# KST-51.net
KiCad netlist of a schematic drawn in Altium Designer
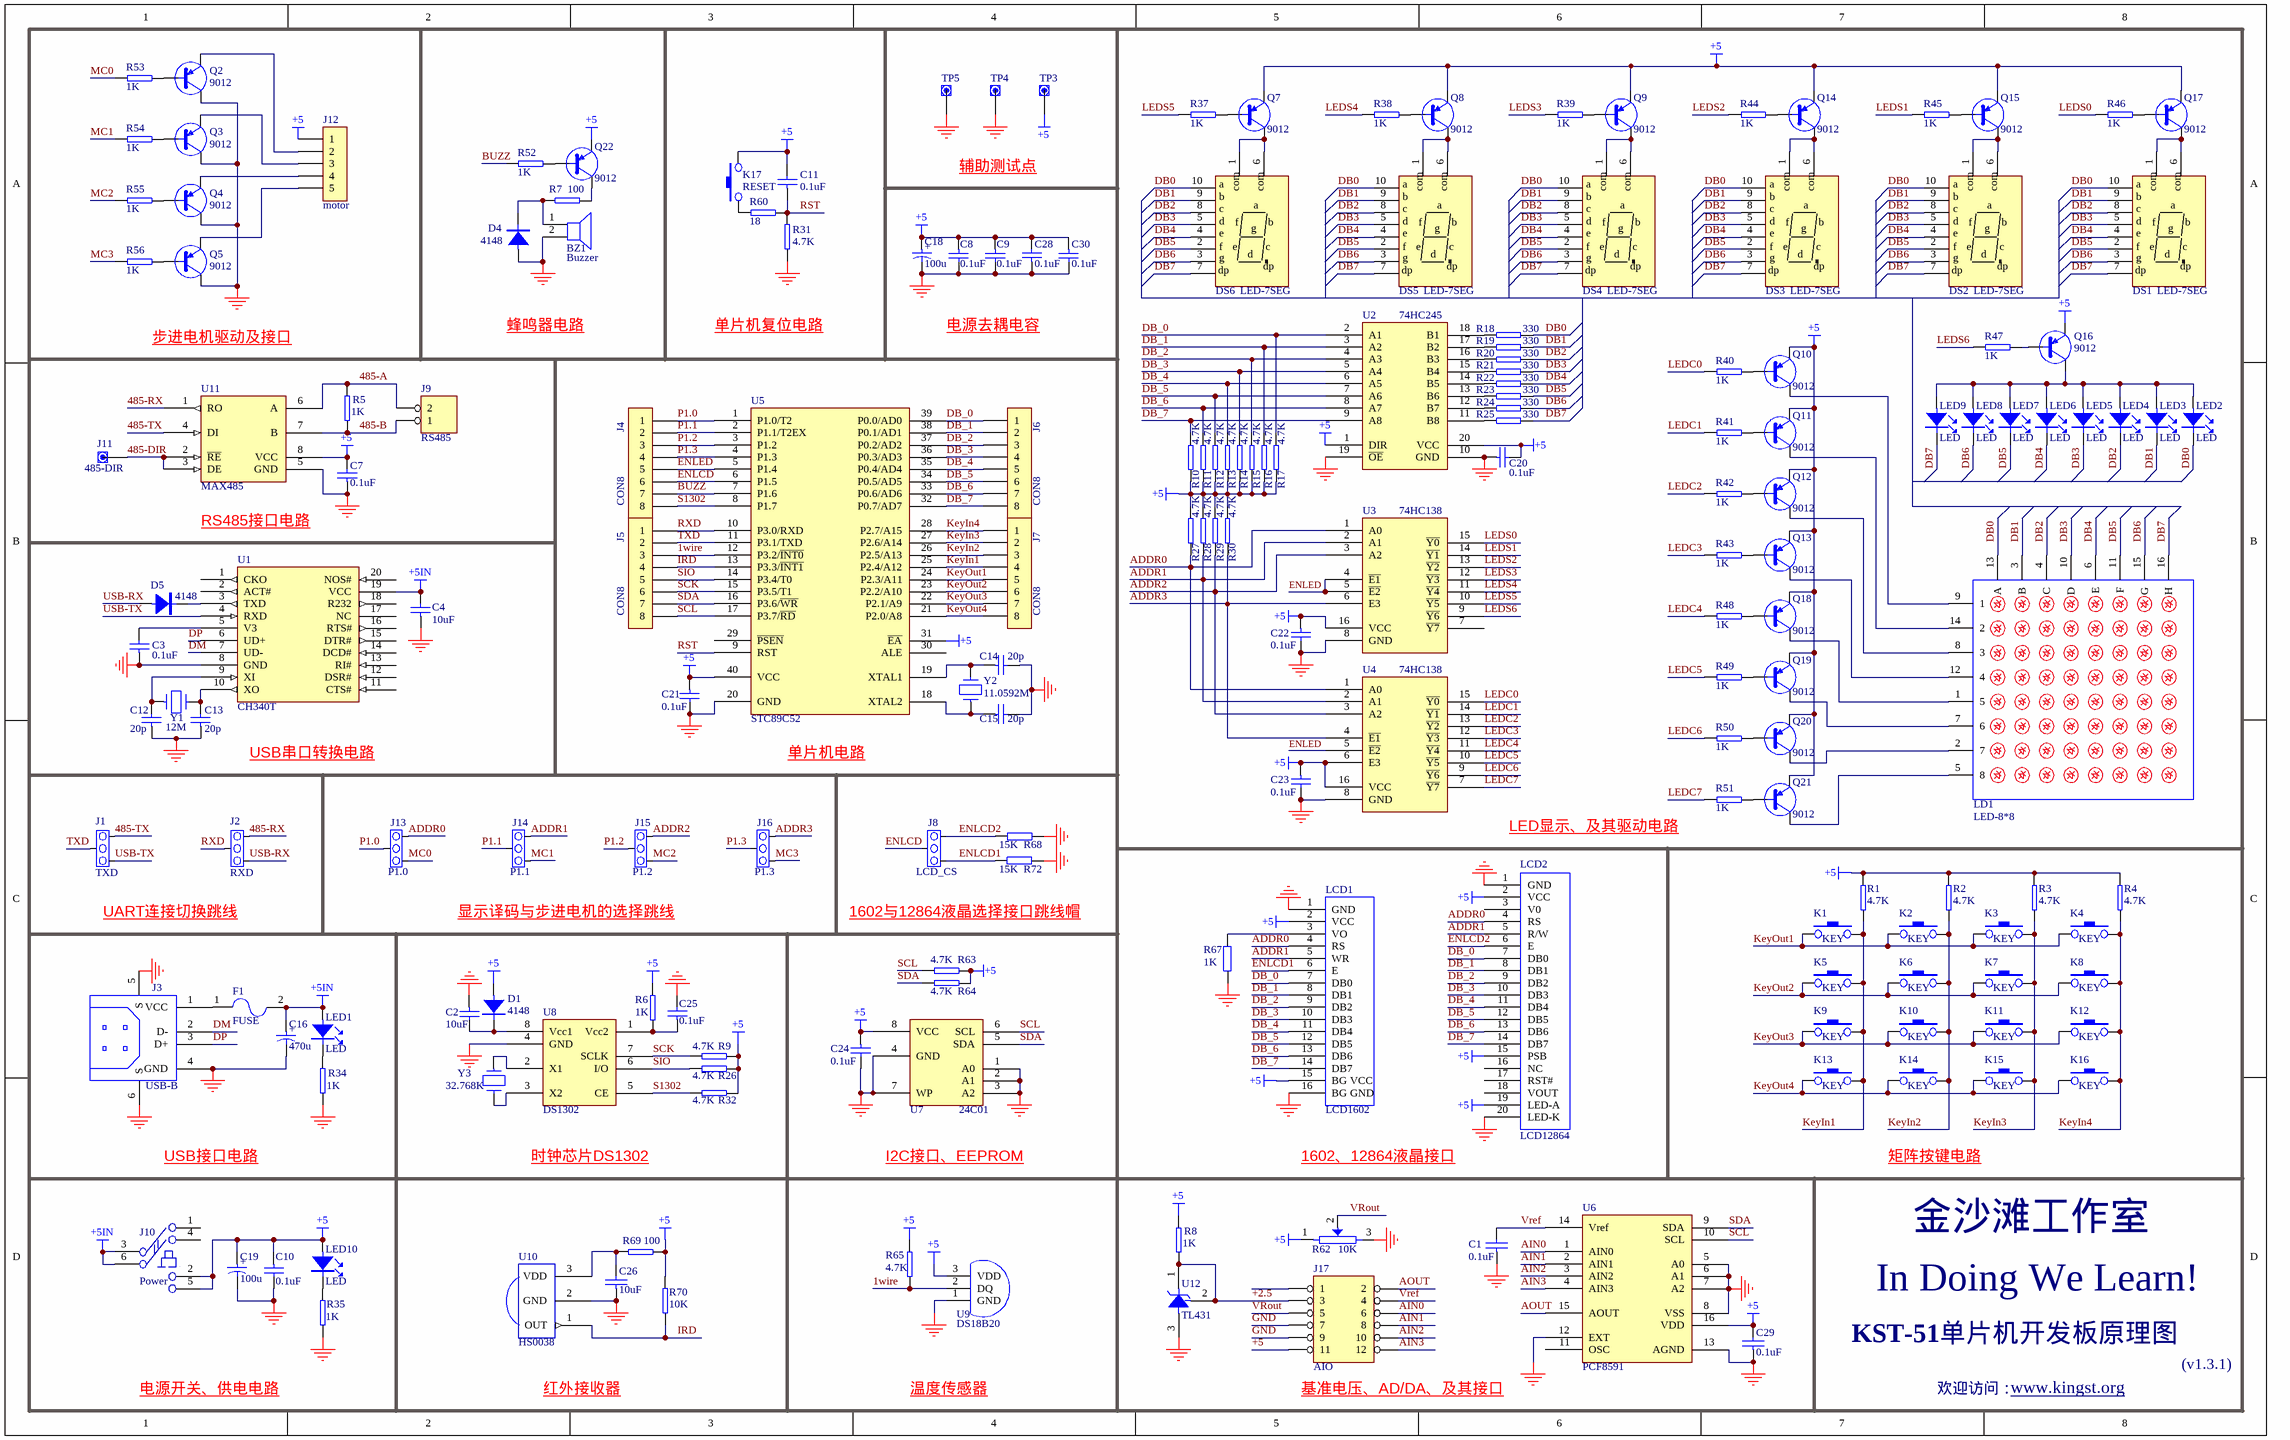
[diagram p0: KST-51开发板原理图.SchDoc]

(export (version "E")
  (design (tool "Eeschema 10.0.6"))
  (components
    (comp (ref "BZ1") (value "Buzzer") (footprint "BUZZ-2") (libsource (lib "*") (part "SPEAKER")))
    (comp (ref "C1")
      (value "0.1uF")
      (footprint "0805C")
      (description "Capacitor")
      (libsource (lib "") (part "CAP_1"))
    )
    (comp (ref "C2") (value "10uF") (footprint "0805C") (libsource (lib "*") (part "CAP")))
    (comp (ref "C3") (value "0.1uF") (footprint "0805C") (libsource (lib "*") (part "CAP")))
    (comp (ref "C4") (value "10uF") (footprint "0805C") (libsource (lib "*") (part "CAP")))
    (comp (ref "C7") (value "0.1uF") (footprint "0805C") (libsource (lib "*") (part "CAP")))
    (comp (ref "C8") (value "0.1uF") (footprint "0805C") (libsource (lib "*") (part "CAP")))
    (comp (ref "C9") (value "0.1uF") (footprint "0805C") (libsource (lib "*") (part "CAP")))
    (comp (ref "C10") (value "0.1uF") (footprint "0805C") (libsource (lib "*") (part "CAP")))
    (comp (ref "C11") (value "0.1uF") (footprint "0805C") (libsource (lib "*") (part "CAP")))
    (comp (ref "C12") (value "20p") (footprint "0805C") (libsource (lib "*") (part "CAP")))
    (comp (ref "C13") (value "20p") (footprint "0805C") (libsource (lib "*") (part "CAP")))
    (comp (ref "C14") (value "20p") (footprint "0805C") (libsource (lib "*") (part "CAP")))
    (comp (ref "C15") (value "20p") (footprint "0805C") (libsource (lib "*") (part "CAP")))
    (comp (ref "C16") (value "470u") (footprint "RB.1/.24") (libsource (lib "*") (part "CAP-P")))
    (comp (ref "C18") (value "100u") (footprint "RB.09/.2") (libsource (lib "*") (part "CAP-P")))
    (comp (ref "C19") (value "100u") (footprint "RB.09/.2") (libsource (lib "*") (part "CAP-P")))
    (comp (ref "C20") (value "0.1uF") (footprint "0805C") (libsource (lib "*") (part "CAP")))
    (comp (ref "C21") (value "0.1uF") (footprint "0805C") (libsource (lib "*") (part "CAP")))
    (comp (ref "C22") (value "0.1uF") (footprint "0805C") (libsource (lib "*") (part "CAP")))
    (comp (ref "C23") (value "0.1uF") (footprint "0805C") (libsource (lib "*") (part "CAP")))
    (comp (ref "C24") (value "0.1uF") (footprint "0805C") (libsource (lib "*") (part "CAP")))
    (comp (ref "C25") (value "0.1uF") (footprint "0805C") (libsource (lib "*") (part "CAP")))
    (comp (ref "C26")
      (value "10uF")
      (footprint "0805C")
      (description "Capacitor")
      (libsource (lib "") (part "CAP_1"))
    )
    (comp (ref "C28") (value "0.1uF") (footprint "0805C") (libsource (lib "*") (part "CAP")))
    (comp (ref "C29")
      (value "0.1uF")
      (footprint "0805C")
      (description "Capacitor")
      (libsource (lib "") (part "CAP_1"))
    )
    (comp (ref "C30") (value "0.1uF") (footprint "0805C") (libsource (lib "*") (part "CAP")))
    (comp (ref "D1") (value "4148") (footprint "1206D") (libsource (lib "*") (part "DIODE")))
    (comp (ref "D4") (value "4148") (footprint "1206D") (libsource (lib "*") (part "DIODE")))
    (comp (ref "D5") (value "4148") (footprint "1206D") (libsource (lib "*") (part "DIODE")))
    (comp (ref "DS1")
      (value "LED-7SEG")
      (footprint "LED-C7")
      (description "Seven-Segment Display, Right Hand Decimal")
      (libsource (lib "*") (part "LED-7SEG"))
    )
    (comp (ref "DS2")
      (value "LED-7SEG")
      (footprint "LED-C7")
      (description "Seven-Segment Display, Right Hand Decimal")
      (libsource (lib "*") (part "LED-7SEG"))
    )
    (comp (ref "DS3")
      (value "LED-7SEG")
      (footprint "LED-C7")
      (description "Seven-Segment Display, Right Hand Decimal")
      (libsource (lib "*") (part "LED-7SEG"))
    )
    (comp (ref "DS4")
      (value "LED-7SEG")
      (footprint "LED-C7")
      (description "Seven-Segment Display, Right Hand Decimal")
      (libsource (lib "*") (part "LED-7SEG"))
    )
    (comp (ref "DS5")
      (value "LED-7SEG")
      (footprint "LED-C7")
      (description "Seven-Segment Display, Right Hand Decimal")
      (libsource (lib "*") (part "LED-7SEG"))
    )
    (comp (ref "DS6")
      (value "LED-7SEG")
      (footprint "LED-C7")
      (description "Seven-Segment Display, Right Hand Decimal")
      (libsource (lib "*") (part "LED-7SEG"))
    )
    (comp (ref "F1") (value "FUSE") (footprint "1812") (libsource (lib "*") (part "FUSE")))
    (comp (ref "J1") (value "TXD") (footprint "JP3*1") (libsource (lib "*") (part "JP-3")))
    (comp (ref "J2") (value "RXD") (footprint "JP3*1") (libsource (lib "*") (part "JP-3")))
    (comp (ref "J3")
      (value "USB-B")
      (footprint "USB-B")
      (description "USB B型插座")
      (libsource (lib "*") (part "USB-B"))
    )
    (comp (ref "J4")
      (value "CON8")
      (footprint "SIP8")
      (description "Connector")
      (libsource (lib "") (part "CON8_1"))
    )
    (comp (ref "J5")
      (value "CON8")
      (footprint "SIP8")
      (description "Connector")
      (libsource (lib "") (part "CON8_1"))
    )
    (comp (ref "J6")
      (value "CON8")
      (footprint "SIP8")
      (description "Connector")
      (libsource (lib "*") (part "CON8"))
    )
    (comp (ref "J7")
      (value "CON8")
      (footprint "SIP8")
      (description "Connector")
      (libsource (lib "*") (part "CON8"))
    )
    (comp (ref "J8") (value "LCD_CS") (footprint "JP3*1") (libsource (lib "*") (part "JP-3")))
    (comp (ref "J9")
      (value "RS485")
      (footprint "PLUG2-5.08")
      (description "Connector 2p")
      (libsource (lib "schOthers") (part "CON2"))
    )
    (comp (ref "J10")
      (value "Power")
      (description "Self-locking button")
      (libsource (lib "schOthers") (part "KEY-SL"))
    )
    (comp (ref "J11")
      (value "485-DIR")
      (footprint "TP")
      (description "Test Point")
      (libsource (lib "schOthers") (part "TP"))
    )
    (comp (ref "J12")
      (value "motor")
      (footprint "PLUG-S5")
      (description "Connector")
      (libsource (lib "*") (part "CON5"))
    )
    (comp (ref "J13") (value "P1.0") (footprint "JP3*1") (libsource (lib "*") (part "JP-3")))
    (comp (ref "J14") (value "P1.1") (footprint "JP3*1") (libsource (lib "*") (part "JP-3")))
    (comp (ref "J15") (value "P1.2") (footprint "JP3*1") (libsource (lib "*") (part "JP-3")))
    (comp (ref "J16") (value "P1.3") (footprint "JP3*1") (libsource (lib "*") (part "JP-3")))
    (comp (ref "J17")
      (value "AIO")
      (footprint "IDC6X2-M")
      (description "Connector 6*2p")
      (libsource (lib "schOthers") (part "CON6X2"))
    )
    (comp (ref "K1") (value "KEY") (footprint "KEY-6*6") (libsource (lib "*") (part "KEY")))
    (comp (ref "K2") (value "KEY") (footprint "KEY-6*6") (libsource (lib "*") (part "KEY")))
    (comp (ref "K3") (value "KEY") (footprint "KEY-6*6") (libsource (lib "*") (part "KEY")))
    (comp (ref "K4") (value "KEY") (footprint "KEY-6*6") (libsource (lib "*") (part "KEY")))
    (comp (ref "K5") (value "KEY") (footprint "KEY-6*6") (libsource (lib "*") (part "KEY")))
    (comp (ref "K6") (value "KEY") (footprint "KEY-6*6") (libsource (lib "*") (part "KEY")))
    (comp (ref "K7") (value "KEY") (footprint "KEY-6*6") (libsource (lib "*") (part "KEY")))
    (comp (ref "K8") (value "KEY") (footprint "KEY-6*6") (libsource (lib "*") (part "KEY")))
    (comp (ref "K9") (value "KEY") (footprint "KEY-6*6") (libsource (lib "*") (part "KEY")))
    (comp (ref "K10") (value "KEY") (footprint "KEY-6*6") (libsource (lib "*") (part "KEY")))
    (comp (ref "K11") (value "KEY") (footprint "KEY-6*6") (libsource (lib "*") (part "KEY")))
    (comp (ref "K12") (value "KEY") (footprint "KEY-6*6") (libsource (lib "*") (part "KEY")))
    (comp (ref "K13") (value "KEY") (footprint "KEY-6*6") (libsource (lib "*") (part "KEY")))
    (comp (ref "K14") (value "KEY") (footprint "KEY-6*6") (libsource (lib "*") (part "KEY")))
    (comp (ref "K15") (value "KEY") (footprint "KEY-6*6") (libsource (lib "*") (part "KEY")))
    (comp (ref "K16") (value "KEY") (footprint "KEY-6*6") (libsource (lib "*") (part "KEY")))
    (comp (ref "K17") (value "RESET") (footprint "KEY-6*6") (libsource (lib "*") (part "KEY")))
    (comp (ref "LCD1") (value "LCD1602") (footprint "LCD1602") (libsource (lib "*") (part "LCD1602")))
    (comp (ref "LCD2")
      (value "LCD12864")
      (footprint "SIP20")
      (description "20pin 128*64 LCD")
      (libsource (lib "schOthers") (part "LCD-12864"))
    )
    (comp (ref "LD1") (value "LED-8*8") (footprint "LED-8*8") (libsource (lib "*") (part "LED-8*8")))
    (comp (ref "LED1") (value "LED") (footprint "0805LED") (libsource (lib "*") (part "LED")))
    (comp (ref "LED2") (value "LED") (footprint "0805LED") (libsource (lib "*") (part "LED")))
    (comp (ref "LED3") (value "LED") (footprint "0805LED") (libsource (lib "*") (part "LED")))
    (comp (ref "LED4") (value "LED") (footprint "0805LED") (libsource (lib "*") (part "LED")))
    (comp (ref "LED5") (value "LED") (footprint "0805LED") (libsource (lib "*") (part "LED")))
    (comp (ref "LED6") (value "LED") (footprint "0805LED") (libsource (lib "*") (part "LED")))
    (comp (ref "LED7") (value "LED") (footprint "0805LED") (libsource (lib "*") (part "LED")))
    (comp (ref "LED8") (value "LED") (footprint "0805LED") (libsource (lib "*") (part "LED")))
    (comp (ref "LED9") (value "LED") (footprint "0805LED") (libsource (lib "*") (part "LED")))
    (comp (ref "LED10") (value "LED") (footprint "0805LED") (libsource (lib "*") (part "LED")))
    (comp (ref "Q2") (value "9012") (footprint "SOT-23-2N") (libsource (lib "*") (part "2N-PNP")))
    (comp (ref "Q3") (value "9012") (footprint "SOT-23-2N") (libsource (lib "*") (part "2N-PNP")))
    (comp (ref "Q4") (value "9012") (footprint "SOT-23-2N") (libsource (lib "*") (part "2N-PNP")))
    (comp (ref "Q5") (value "9012") (footprint "SOT-23-2N") (libsource (lib "*") (part "2N-PNP")))
    (comp (ref "Q7") (value "9012") (footprint "SOT-23-2N") (libsource (lib "*") (part "2N-PNP")))
    (comp (ref "Q8") (value "9012") (footprint "SOT-23-2N") (libsource (lib "*") (part "2N-PNP")))
    (comp (ref "Q9") (value "9012") (footprint "SOT-23-2N") (libsource (lib "*") (part "2N-PNP")))
    (comp (ref "Q10") (value "9012") (footprint "SOT-23-2N") (libsource (lib "*") (part "2N-PNP")))
    (comp (ref "Q11") (value "9012") (footprint "SOT-23-2N") (libsource (lib "*") (part "2N-PNP")))
    (comp (ref "Q12") (value "9012") (footprint "SOT-23-2N") (libsource (lib "*") (part "2N-PNP")))
    (comp (ref "Q13") (value "9012") (footprint "SOT-23-2N") (libsource (lib "*") (part "2N-PNP")))
    (comp (ref "Q14") (value "9012") (footprint "SOT-23-2N") (libsource (lib "*") (part "2N-PNP")))
    (comp (ref "Q15") (value "9012") (footprint "SOT-23-2N") (libsource (lib "*") (part "2N-PNP")))
    (comp (ref "Q16") (value "9012") (footprint "SOT-23-2N") (libsource (lib "*") (part "2N-PNP")))
    (comp (ref "Q17") (value "9012") (footprint "SOT-23-2N") (libsource (lib "*") (part "2N-PNP")))
    (comp (ref "Q18") (value "9012") (footprint "SOT-23-2N") (libsource (lib "*") (part "2N-PNP")))
    (comp (ref "Q19") (value "9012") (footprint "SOT-23-2N") (libsource (lib "*") (part "2N-PNP")))
    (comp (ref "Q20") (value "9012") (footprint "SOT-23-2N") (libsource (lib "*") (part "2N-PNP")))
    (comp (ref "Q21") (value "9012") (footprint "SOT-23-2N") (libsource (lib "*") (part "2N-PNP")))
    (comp (ref "Q22") (value "9012") (footprint "SOT-23-2N") (libsource (lib "*") (part "2N-PNP")))
    (comp (ref "R1") (value "4.7K") (footprint "0805") (libsource (lib "*") (part "RES2")))
    (comp (ref "R2") (value "4.7K") (footprint "0805") (libsource (lib "*") (part "RES2")))
    (comp (ref "R3") (value "4.7K") (footprint "0805") (libsource (lib "*") (part "RES2")))
    (comp (ref "R4") (value "4.7K") (footprint "0805") (libsource (lib "*") (part "RES2")))
    (comp (ref "R5") (value "1K") (footprint "0805") (libsource (lib "*") (part "RES2")))
    (comp (ref "R6") (value "1K") (footprint "0805") (libsource (lib "*") (part "RES2")))
    (comp (ref "R7") (value "100") (footprint "0805") (libsource (lib "*") (part "RES2")))
    (comp (ref "R8") (value "1K") (footprint "0805") (libsource (lib "*") (part "RES2")))
    (comp (ref "R9") (value "4.7K") (footprint "0805") (libsource (lib "*") (part "RES2")))
    (comp (ref "R10") (value "4.7K") (footprint "0805") (libsource (lib "*") (part "RES2")))
    (comp (ref "R11") (value "4.7K") (footprint "0805") (libsource (lib "*") (part "RES2")))
    (comp (ref "R12") (value "4.7K") (footprint "0805") (libsource (lib "*") (part "RES2")))
    (comp (ref "R13") (value "4.7K") (footprint "0805") (libsource (lib "*") (part "RES2")))
    (comp (ref "R14") (value "4.7K") (footprint "0805") (libsource (lib "*") (part "RES2")))
    (comp (ref "R15") (value "4.7K") (footprint "0805") (libsource (lib "*") (part "RES2")))
    (comp (ref "R16") (value "4.7K") (footprint "0805") (libsource (lib "*") (part "RES2")))
    (comp (ref "R17") (value "4.7K") (footprint "0805") (libsource (lib "*") (part "RES2")))
    (comp (ref "R18") (value "330") (footprint "0805") (libsource (lib "*") (part "RES2")))
    (comp (ref "R19") (value "330") (footprint "0805") (libsource (lib "*") (part "RES2")))
    (comp (ref "R20") (value "330") (footprint "0805") (libsource (lib "*") (part "RES2")))
    (comp (ref "R21") (value "330") (footprint "0805") (libsource (lib "*") (part "RES2")))
    (comp (ref "R22") (value "330") (footprint "0805") (libsource (lib "*") (part "RES2")))
    (comp (ref "R23") (value "330") (footprint "0805") (libsource (lib "*") (part "RES2")))
    (comp (ref "R24") (value "330") (footprint "0805") (libsource (lib "*") (part "RES2")))
    (comp (ref "R25") (value "330") (footprint "0805") (libsource (lib "*") (part "RES2")))
    (comp (ref "R26") (value "4.7K") (footprint "0805") (libsource (lib "*") (part "RES2")))
    (comp (ref "R27") (value "4.7K") (footprint "0805") (libsource (lib "*") (part "RES2")))
    (comp (ref "R28") (value "4.7K") (footprint "0805") (libsource (lib "*") (part "RES2")))
    (comp (ref "R29") (value "4.7K") (footprint "0805") (libsource (lib "*") (part "RES2")))
    (comp (ref "R30") (value "4.7K") (footprint "0805") (libsource (lib "*") (part "RES2")))
    (comp (ref "R31") (value "4.7K") (footprint "0805") (libsource (lib "*") (part "RES2")))
    (comp (ref "R32") (value "4.7K") (footprint "0805") (libsource (lib "*") (part "RES2")))
    (comp (ref "R34") (value "1K") (footprint "0805") (libsource (lib "*") (part "RES2")))
    (comp (ref "R35") (value "1K") (footprint "0805") (libsource (lib "*") (part "RES2")))
    (comp (ref "R37") (value "1K") (footprint "0805") (libsource (lib "*") (part "RES2")))
    (comp (ref "R38") (value "1K") (footprint "0805") (libsource (lib "*") (part "RES2")))
    (comp (ref "R39") (value "1K") (footprint "0805") (libsource (lib "*") (part "RES2")))
    (comp (ref "R40") (value "1K") (footprint "0805") (libsource (lib "*") (part "RES2")))
    (comp (ref "R41") (value "1K") (footprint "0805") (libsource (lib "*") (part "RES2")))
    (comp (ref "R42") (value "1K") (footprint "0805") (libsource (lib "*") (part "RES2")))
    (comp (ref "R43") (value "1K") (footprint "0805") (libsource (lib "*") (part "RES2")))
    (comp (ref "R44") (value "1K") (footprint "0805") (libsource (lib "*") (part "RES2")))
    (comp (ref "R45") (value "1K") (footprint "0805") (libsource (lib "*") (part "RES2")))
    (comp (ref "R46") (value "1K") (footprint "0805") (libsource (lib "*") (part "RES2")))
    (comp (ref "R47") (value "1K") (footprint "0805") (libsource (lib "*") (part "RES2")))
    (comp (ref "R48") (value "1K") (footprint "0805") (libsource (lib "*") (part "RES2")))
    (comp (ref "R49") (value "1K") (footprint "0805") (libsource (lib "*") (part "RES2")))
    (comp (ref "R50") (value "1K") (footprint "0805") (libsource (lib "*") (part "RES2")))
    (comp (ref "R51") (value "1K") (footprint "0805") (libsource (lib "*") (part "RES2")))
    (comp (ref "R52") (value "1K") (footprint "0805") (libsource (lib "*") (part "RES2")))
    (comp (ref "R53") (value "1K") (footprint "0805") (libsource (lib "*") (part "RES2")))
    (comp (ref "R54") (value "1K") (footprint "0805") (libsource (lib "*") (part "RES2")))
    (comp (ref "R55") (value "1K") (footprint "0805") (libsource (lib "*") (part "RES2")))
    (comp (ref "R56") (value "1K") (footprint "0805") (libsource (lib "*") (part "RES2")))
    (comp (ref "R60") (value "18") (footprint "0805") (libsource (lib "*") (part "RES2")))
    (comp (ref "R62") (value "10K") (footprint "VR6") (libsource (lib "*") (part "RES-V")))
    (comp (ref "R63") (value "4.7K") (footprint "0805") (libsource (lib "*") (part "RES2")))
    (comp (ref "R64") (value "4.7K") (footprint "0805") (libsource (lib "*") (part "RES2")))
    (comp (ref "R65") (value "4.7K") (footprint "0805") (libsource (lib "*") (part "RES2")))
    (comp (ref "R67") (value "1K") (footprint "0805") (description "电阻") (libsource (lib "") (part "RES2_1")))
    (comp (ref "R68")
      (value "15K")
      (footprint "0805")
      (description "电阻")
      (libsource (lib "") (part "RES2_1"))
    )
    (comp (ref "R69") (value "100") (footprint "0805") (libsource (lib "*") (part "RES2")))
    (comp (ref "R70") (value "10K") (footprint "0805") (libsource (lib "*") (part "RES2")))
    (comp (ref "R72")
      (value "15K")
      (footprint "0805")
      (description "电阻")
      (libsource (lib "") (part "RES2_1"))
    )
    (comp (ref "TP3")
      (value "+5V")
      (footprint "TP-S")
      (description "电路测试点")
      (libsource (lib "*") (part "TP"))
    )
    (comp (ref "TP4")
      (value "GND")
      (footprint "TP-S")
      (description "电路测试点")
      (libsource (lib "*") (part "TP"))
    )
    (comp (ref "TP5")
      (value "GND")
      (footprint "TP-S")
      (description "电路测试点")
      (libsource (lib "*") (part "TP"))
    )
    (comp (ref "U1")
      (value "CH340T")
      (footprint "SSOP20-5.3")
      (description "USB to UART Bridge Controller")
      (libsource (lib "schChips") (part "CH340T"))
    )
    (comp (ref "U2") (value "74HC245") (footprint "SOP20-400") (libsource (lib "*") (part "74XX245")))
    (comp (ref "U3") (value "74HC138") (footprint "SOP16-240") (libsource (lib "*") (part "74XX138")))
    (comp (ref "U4") (value "74HC138") (footprint "SOP16-240") (libsource (lib "*") (part "74XX138")))
    (comp (ref "U5") (value "STC89C52") (footprint "DIP40-PLUG") (libsource (lib "*") (part "STC89C52")))
    (comp (ref "U6") (value "PCF8591") (footprint "SOP16-400") (libsource (lib "*") (part "PCF8591")))
    (comp (ref "U7") (value "24C01") (footprint "SOP8") (libsource (lib "*") (part "24C01")))
    (comp (ref "U8") (value "DS1302") (footprint "SOP8") (libsource (lib "*") (part "DS1302")))
    (comp (ref "U9") (value "DS18B20") (footprint "TO-92") (libsource (lib "*") (part "DS18B20")))
    (comp (ref "U10")
      (value "HS0038")
      (footprint "HS0038")
      (description "Infrared Receiver")
      (libsource (lib "schChips") (part "HS0038"))
    )
    (comp (ref "U11")
      (value "MAX485")
      (footprint "SOP8-3.9")
      (description "RS-485 Transceiver")
      (libsource (lib "schChips") (part "MAX485"))
    )
    (comp (ref "U12")
      (value "TL431")
      (footprint "SOT-23-3L")
      (description "Adjustable precision shunt regulator, 3p SOT")
      (libsource (lib "schChips") (part "TL431-SOT"))
    )
    (comp (ref "Y1") (value "12M") (footprint "XTAL") (libsource (lib "*") (part "CRYSTAL")))
    (comp (ref "Y2") (value "11.0592M") (footprint "XTAL") (libsource (lib "*") (part "CRYSTAL")))
    (comp (ref "Y3") (value "32.768K") (footprint "XTAL2") (libsource (lib "*") (part "CRYSTAL")))
  )
  (nets
    (net (code "1") (name "+5") (class "Default")
      (node (ref "C10") (pin "1") (pinfunction "1_1") (pintype "passive"))
      (node (ref "C11") (pin "2") (pinfunction "2_2") (pintype "passive"))
      (node (ref "C18") (pin "1") (pinfunction "1_1") (pintype "passive"))
      (node (ref "C19") (pin "1") (pinfunction "1_1") (pintype "passive"))
      (node (ref "C20") (pin "2") (pinfunction "2_2") (pintype "passive"))
      (node (ref "C21") (pin "1") (pinfunction "1_1") (pintype "passive"))
      (node (ref "C22") (pin "1") (pinfunction "1_1") (pintype "passive"))
      (node (ref "C23") (pin "1") (pinfunction "1_1") (pintype "passive"))
      (node (ref "C24") (pin "1") (pinfunction "1_1") (pintype "passive"))
      (node (ref "C28") (pin "2") (pinfunction "2_2") (pintype "passive"))
      (node (ref "C29") (pin "2") (pinfunction "2_2") (pintype "passive"))
      (node (ref "C30") (pin "1") (pinfunction "1_1") (pintype "passive"))
      (node (ref "C7") (pin "2") (pinfunction "2_2") (pintype "passive"))
      (node (ref "C8") (pin "1") (pinfunction "1_1") (pintype "passive"))
      (node (ref "C9") (pin "1") (pinfunction "1_1") (pintype "passive"))
      (node (ref "D1") (pin "A") (pinfunction "1_A") (pintype "passive"))
      (node (ref "J10") (pin "2") (pinfunction "2_2") (pintype "passive"))
      (node (ref "J10") (pin "5") (pinfunction "5_5") (pintype "passive"))
      (node (ref "J12") (pin "1") (pinfunction "1_1") (pintype "passive"))
      (node (ref "J17") (pin "11") (pinfunction "11_11") (pintype "passive"))
      (node (ref "K17") (pin "2") (pinfunction "2_2") (pintype "passive"))
      (node (ref "LCD1") (pin "15") (pinfunction "BG_VCC_15") (pintype "passive"))
      (node (ref "LCD1") (pin "2") (pinfunction "VCC_2") (pintype "passive"))
      (node (ref "LCD2") (pin "15") (pinfunction "PSB_15") (pintype "power_in"))
      (node (ref "LCD2") (pin "19") (pinfunction "LED-A_19") (pintype "power_in"))
      (node (ref "LCD2") (pin "2") (pinfunction "VCC_2") (pintype "power_in"))
      (node (ref "LED10") (pin "A") (pinfunction "1_A") (pintype "passive"))
      (node (ref "Q10") (pin "E") (pinfunction "E_E") (pintype "passive"))
      (node (ref "Q11") (pin "E") (pinfunction "E_E") (pintype "passive"))
      (node (ref "Q12") (pin "E") (pinfunction "E_E") (pintype "passive"))
      (node (ref "Q13") (pin "E") (pinfunction "E_E") (pintype "passive"))
      (node (ref "Q14") (pin "E") (pinfunction "E_E") (pintype "passive"))
      (node (ref "Q15") (pin "E") (pinfunction "E_E") (pintype "passive"))
      (node (ref "Q16") (pin "E") (pinfunction "E_E") (pintype "passive"))
      (node (ref "Q17") (pin "E") (pinfunction "E_E") (pintype "passive"))
      (node (ref "Q18") (pin "E") (pinfunction "E_E") (pintype "passive"))
      (node (ref "Q19") (pin "E") (pinfunction "E_E") (pintype "passive"))
      (node (ref "Q20") (pin "E") (pinfunction "E_E") (pintype "passive"))
      (node (ref "Q21") (pin "E") (pinfunction "E_E") (pintype "passive"))
      (node (ref "Q22") (pin "E") (pinfunction "E_E") (pintype "passive"))
      (node (ref "Q7") (pin "E") (pinfunction "E_E") (pintype "passive"))
      (node (ref "Q8") (pin "E") (pinfunction "E_E") (pintype "passive"))
      (node (ref "Q9") (pin "E") (pinfunction "E_E") (pintype "passive"))
      (node (ref "R1") (pin "2") (pinfunction "2_2") (pintype "passive"))
      (node (ref "R10") (pin "1") (pinfunction "1_1") (pintype "passive"))
      (node (ref "R11") (pin "1") (pinfunction "1_1") (pintype "passive"))
      (node (ref "R12") (pin "1") (pinfunction "1_1") (pintype "passive"))
      (node (ref "R13") (pin "1") (pinfunction "1_1") (pintype "passive"))
      (node (ref "R14") (pin "1") (pinfunction "1_1") (pintype "passive"))
      (node (ref "R15") (pin "1") (pinfunction "1_1") (pintype "passive"))
      (node (ref "R16") (pin "1") (pinfunction "1_1") (pintype "passive"))
      (node (ref "R17") (pin "1") (pinfunction "1_1") (pintype "passive"))
      (node (ref "R2") (pin "2") (pinfunction "2_2") (pintype "passive"))
      (node (ref "R26") (pin "2") (pinfunction "2_2") (pintype "passive"))
      (node (ref "R27") (pin "2") (pinfunction "2_2") (pintype "passive"))
      (node (ref "R28") (pin "2") (pinfunction "2_2") (pintype "passive"))
      (node (ref "R29") (pin "2") (pinfunction "2_2") (pintype "passive"))
      (node (ref "R3") (pin "2") (pinfunction "2_2") (pintype "passive"))
      (node (ref "R30") (pin "2") (pinfunction "2_2") (pintype "passive"))
      (node (ref "R32") (pin "2") (pinfunction "2_2") (pintype "passive"))
      (node (ref "R4") (pin "2") (pinfunction "2_2") (pintype "passive"))
      (node (ref "R6") (pin "2") (pinfunction "2_2") (pintype "passive"))
      (node (ref "R62") (pin "1") (pinfunction "1_1") (pintype "passive"))
      (node (ref "R63") (pin "2") (pinfunction "2_2") (pintype "passive"))
      (node (ref "R64") (pin "2") (pinfunction "2_2") (pintype "passive"))
      (node (ref "R65") (pin "2") (pinfunction "2_2") (pintype "passive"))
      (node (ref "R69") (pin "2") (pinfunction "2_2") (pintype "passive"))
      (node (ref "R70") (pin "1") (pinfunction "1_1") (pintype "passive"))
      (node (ref "R8") (pin "2") (pinfunction "2_2") (pintype "passive"))
      (node (ref "R9") (pin "2") (pinfunction "2_2") (pintype "passive"))
      (node (ref "TP3") (pin "1") (pintype "passive"))
      (node (ref "U11") (pin "8") (pinfunction "VCC_8") (pintype "power_in"))
      (node (ref "U2") (pin "1") (pinfunction "DIR_1") (pintype "passive"))
      (node (ref "U2") (pin "20") (pinfunction "VCC_20") (pintype "passive"))
      (node (ref "U3") (pin "16") (pinfunction "VCC_16") (pintype "passive"))
      (node (ref "U4") (pin "16") (pinfunction "VCC_16") (pintype "passive"))
      (node (ref "U4") (pin "6") (pinfunction "E3_6") (pintype "passive"))
      (node (ref "U5") (pin "31") (pinfunction "~{EA}_31") (pintype "passive"))
      (node (ref "U5") (pin "40") (pinfunction "VCC_40") (pintype "passive"))
      (node (ref "U6") (pin "16") (pinfunction "VDD_16") (pintype "passive"))
      (node (ref "U7") (pin "8") (pinfunction "VCC_8") (pintype "passive"))
      (node (ref "U9") (pin "3") (pinfunction "VDD_3") (pintype "passive"))
    )
    (net (code "2") (name "+5IN") (class "Default")
      (node (ref "C16") (pin "1") (pinfunction "1_1") (pintype "passive"))
      (node (ref "C4") (pin "2") (pinfunction "2_2") (pintype "passive"))
      (node (ref "F1") (pin "2") (pinfunction "2_2") (pintype "passive"))
      (node (ref "J10") (pin "3") (pinfunction "3_3") (pintype "passive"))
      (node (ref "J10") (pin "6") (pinfunction "6_6") (pintype "passive"))
      (node (ref "LED1") (pin "A") (pinfunction "1_A") (pintype "passive"))
      (node (ref "U1") (pin "19") (pinfunction "VCC_19") (pintype "power_in"))
    )
    (net (code "3") (name "/+2.5") (class "Default")
      (node (ref "J17") (pin "3") (pinfunction "3_3") (pintype "passive"))
      (node (ref "R8") (pin "1") (pinfunction "1_1") (pintype "passive"))
      (node (ref "U12") (pin "1") (pinfunction "CATHODE_1") (pintype "power_in"))
      (node (ref "U12") (pin "2") (pinfunction "REF_2") (pintype "passive"))
    )
    (net (code "4") (name "/1wire") (class "Default")
      (node (ref "J5") (pin "3") (pinfunction "3_3") (pintype "passive"))
      (node (ref "R65") (pin "1") (pinfunction "1_1") (pintype "passive"))
      (node (ref "U5") (pin "12") (pinfunction "P3.2/~{INT0}_12") (pintype "passive"))
      (node (ref "U9") (pin "2") (pinfunction "DQ_2") (pintype "passive"))
    )
    (net (code "5") (name "/485-A") (class "Default")
      (node (ref "J9") (pin "2") (pinfunction "2_2") (pintype "passive"))
      (node (ref "R5") (pin "1") (pinfunction "1_1") (pintype "passive"))
      (node (ref "U11") (pin "6") (pinfunction "A_6") (pintype "passive"))
    )
    (net (code "6") (name "/485-B") (class "Default")
      (node (ref "J9") (pin "1") (pinfunction "1_1") (pintype "passive"))
      (node (ref "R5") (pin "2") (pinfunction "2_2") (pintype "passive"))
      (node (ref "U11") (pin "7") (pinfunction "B_7") (pintype "passive"))
    )
    (net (code "7") (name "/485-DIR") (class "Default")
      (node (ref "J11") (pin "1") (pintype "passive"))
      (node (ref "U11") (pin "2") (pinfunction "~{RE}_2") (pintype "input"))
      (node (ref "U11") (pin "3") (pinfunction "DE_3") (pintype "input"))
    )
    (net (code "8") (name "/485-RX") (class "Default")
      (node (ref "J2") (pin "3") (pinfunction "3_3") (pintype "passive"))
      (node (ref "U11") (pin "1") (pinfunction "RO_1") (pintype "output"))
    )
    (net (code "9") (name "/485-TX") (class "Default")
      (node (ref "J1") (pin "3") (pinfunction "3_3") (pintype "passive"))
      (node (ref "U11") (pin "4") (pinfunction "DI_4") (pintype "input"))
    )
    (net (code "10") (name "/ADDR0") (class "Default")
      (node (ref "J13") (pin "1") (pinfunction "1_1") (pintype "passive"))
      (node (ref "LCD1") (pin "4") (pinfunction "RS_4") (pintype "passive"))
      (node (ref "LCD2") (pin "4") (pinfunction "RS_4") (pintype "power_in"))
      (node (ref "R27") (pin "1") (pinfunction "1_1") (pintype "passive"))
      (node (ref "U3") (pin "1") (pinfunction "A0_1") (pintype "passive"))
      (node (ref "U4") (pin "1") (pinfunction "A0_1") (pintype "passive"))
    )
    (net (code "11") (name "/ADDR1") (class "Default")
      (node (ref "J14") (pin "1") (pinfunction "1_1") (pintype "passive"))
      (node (ref "LCD1") (pin "5") (pinfunction "WR_5") (pintype "passive"))
      (node (ref "LCD2") (pin "5") (pinfunction "R/W_5") (pintype "power_in"))
      (node (ref "R28") (pin "1") (pinfunction "1_1") (pintype "passive"))
      (node (ref "U3") (pin "2") (pinfunction "A1_2") (pintype "passive"))
      (node (ref "U4") (pin "2") (pinfunction "A1_2") (pintype "passive"))
    )
    (net (code "12") (name "/ADDR2") (class "Default")
      (node (ref "J15") (pin "1") (pinfunction "1_1") (pintype "passive"))
      (node (ref "R29") (pin "1") (pinfunction "1_1") (pintype "passive"))
      (node (ref "U3") (pin "3") (pinfunction "A2_3") (pintype "passive"))
      (node (ref "U4") (pin "3") (pinfunction "A2_3") (pintype "passive"))
    )
    (net (code "13") (name "/ADDR3") (class "Default")
      (node (ref "J16") (pin "1") (pinfunction "1_1") (pintype "passive"))
      (node (ref "R30") (pin "1") (pinfunction "1_1") (pintype "passive"))
      (node (ref "U3") (pin "6") (pinfunction "E3_6") (pintype "passive"))
      (node (ref "U4") (pin "4") (pinfunction "~{E1}_4") (pintype "passive"))
    )
    (net (code "14") (name "/AIN0") (class "Default")
      (node (ref "J17") (pin "6") (pinfunction "6_6") (pintype "passive"))
      (node (ref "U6") (pin "1") (pinfunction "AIN0_1") (pintype "passive"))
    )
    (net (code "15") (name "/AIN1") (class "Default")
      (node (ref "J17") (pin "8") (pinfunction "8_8") (pintype "passive"))
      (node (ref "U6") (pin "2") (pinfunction "AIN1_2") (pintype "passive"))
    )
    (net (code "16") (name "/AIN2") (class "Default")
      (node (ref "J17") (pin "10") (pinfunction "10_10") (pintype "passive"))
      (node (ref "U6") (pin "3") (pinfunction "AIN2_3") (pintype "passive"))
    )
    (net (code "17") (name "/AIN3") (class "Default")
      (node (ref "J17") (pin "12") (pinfunction "12_12") (pintype "passive"))
      (node (ref "U6") (pin "4") (pinfunction "AIN3_4") (pintype "passive"))
    )
    (net (code "18") (name "/AOUT") (class "Default")
      (node (ref "J17") (pin "2") (pinfunction "2_2") (pintype "passive"))
      (node (ref "U6") (pin "15") (pinfunction "AOUT_15") (pintype "passive"))
    )
    (net (code "19") (name "/BUZZ") (class "Default")
      (node (ref "J4") (pin "7") (pinfunction "7_7") (pintype "passive"))
      (node (ref "R52") (pin "1") (pinfunction "1_1") (pintype "passive"))
      (node (ref "U5") (pin "7") (pinfunction "P1.6_7") (pintype "passive"))
    )
    (net (code "20") (name "/DB0") (class "Default")
      (node (ref "DS1") (pin "10") (pinfunction "a_10") (pintype "passive"))
      (node (ref "DS2") (pin "10") (pinfunction "a_10") (pintype "passive"))
      (node (ref "DS3") (pin "10") (pinfunction "a_10") (pintype "passive"))
      (node (ref "DS4") (pin "10") (pinfunction "a_10") (pintype "passive"))
      (node (ref "DS5") (pin "10") (pinfunction "a_10") (pintype "passive"))
      (node (ref "DS6") (pin "10") (pinfunction "a_10") (pintype "passive"))
      (node (ref "LD1") (pin "13") (pinfunction "A_13") (pintype "passive"))
      (node (ref "LED2") (pin "K") (pinfunction "2_K") (pintype "passive"))
      (node (ref "R18") (pin "1") (pinfunction "1_1") (pintype "passive"))
    )
    (net (code "21") (name "/DB1") (class "Default")
      (node (ref "DS1") (pin "9") (pinfunction "b_9") (pintype "passive"))
      (node (ref "DS2") (pin "9") (pinfunction "b_9") (pintype "passive"))
      (node (ref "DS3") (pin "9") (pinfunction "b_9") (pintype "passive"))
      (node (ref "DS4") (pin "9") (pinfunction "b_9") (pintype "passive"))
      (node (ref "DS5") (pin "9") (pinfunction "b_9") (pintype "passive"))
      (node (ref "DS6") (pin "9") (pinfunction "b_9") (pintype "passive"))
      (node (ref "LD1") (pin "3") (pinfunction "B_3") (pintype "passive"))
      (node (ref "LED3") (pin "K") (pinfunction "2_K") (pintype "passive"))
      (node (ref "R19") (pin "1") (pinfunction "1_1") (pintype "passive"))
    )
    (net (code "22") (name "/DB2") (class "Default")
      (node (ref "DS1") (pin "8") (pinfunction "c_8") (pintype "passive"))
      (node (ref "DS2") (pin "8") (pinfunction "c_8") (pintype "passive"))
      (node (ref "DS3") (pin "8") (pinfunction "c_8") (pintype "passive"))
      (node (ref "DS4") (pin "8") (pinfunction "c_8") (pintype "passive"))
      (node (ref "DS5") (pin "8") (pinfunction "c_8") (pintype "passive"))
      (node (ref "DS6") (pin "8") (pinfunction "c_8") (pintype "passive"))
      (node (ref "LD1") (pin "4") (pinfunction "C_4") (pintype "passive"))
      (node (ref "LED4") (pin "K") (pinfunction "2_K") (pintype "passive"))
      (node (ref "R20") (pin "1") (pinfunction "1_1") (pintype "passive"))
    )
    (net (code "23") (name "/DB3") (class "Default")
      (node (ref "DS1") (pin "5") (pinfunction "d_5") (pintype "passive"))
      (node (ref "DS2") (pin "5") (pinfunction "d_5") (pintype "passive"))
      (node (ref "DS3") (pin "5") (pinfunction "d_5") (pintype "passive"))
      (node (ref "DS4") (pin "5") (pinfunction "d_5") (pintype "passive"))
      (node (ref "DS5") (pin "5") (pinfunction "d_5") (pintype "passive"))
      (node (ref "DS6") (pin "5") (pinfunction "d_5") (pintype "passive"))
      (node (ref "LD1") (pin "10") (pinfunction "D_10") (pintype "passive"))
      (node (ref "LED5") (pin "K") (pinfunction "2_K") (pintype "passive"))
      (node (ref "R21") (pin "1") (pinfunction "1_1") (pintype "passive"))
    )
    (net (code "24") (name "/DB4") (class "Default")
      (node (ref "DS1") (pin "4") (pinfunction "e_4") (pintype "passive"))
      (node (ref "DS2") (pin "4") (pinfunction "e_4") (pintype "passive"))
      (node (ref "DS3") (pin "4") (pinfunction "e_4") (pintype "passive"))
      (node (ref "DS4") (pin "4") (pinfunction "e_4") (pintype "passive"))
      (node (ref "DS5") (pin "4") (pinfunction "e_4") (pintype "passive"))
      (node (ref "DS6") (pin "4") (pinfunction "e_4") (pintype "passive"))
      (node (ref "LD1") (pin "6") (pinfunction "E_6") (pintype "passive"))
      (node (ref "LED6") (pin "K") (pinfunction "2_K") (pintype "passive"))
      (node (ref "R22") (pin "1") (pinfunction "1_1") (pintype "passive"))
    )
    (net (code "25") (name "/DB5") (class "Default")
      (node (ref "DS1") (pin "2") (pinfunction "f_2") (pintype "passive"))
      (node (ref "DS2") (pin "2") (pinfunction "f_2") (pintype "passive"))
      (node (ref "DS3") (pin "2") (pinfunction "f_2") (pintype "passive"))
      (node (ref "DS4") (pin "2") (pinfunction "f_2") (pintype "passive"))
      (node (ref "DS5") (pin "2") (pinfunction "f_2") (pintype "passive"))
      (node (ref "DS6") (pin "2") (pinfunction "f_2") (pintype "passive"))
      (node (ref "LD1") (pin "11") (pinfunction "F_11") (pintype "passive"))
      (node (ref "LED7") (pin "K") (pinfunction "2_K") (pintype "passive"))
      (node (ref "R23") (pin "1") (pinfunction "1_1") (pintype "passive"))
    )
    (net (code "26") (name "/DB6") (class "Default")
      (node (ref "DS1") (pin "3") (pinfunction "g_3") (pintype "passive"))
      (node (ref "DS2") (pin "3") (pinfunction "g_3") (pintype "passive"))
      (node (ref "DS3") (pin "3") (pinfunction "g_3") (pintype "passive"))
      (node (ref "DS4") (pin "3") (pinfunction "g_3") (pintype "passive"))
      (node (ref "DS5") (pin "3") (pinfunction "g_3") (pintype "passive"))
      (node (ref "DS6") (pin "3") (pinfunction "g_3") (pintype "passive"))
      (node (ref "LD1") (pin "15") (pinfunction "G_15") (pintype "passive"))
      (node (ref "LED8") (pin "K") (pinfunction "2_K") (pintype "passive"))
      (node (ref "R24") (pin "1") (pinfunction "1_1") (pintype "passive"))
    )
    (net (code "27") (name "/DB7") (class "Default")
      (node (ref "DS1") (pin "7") (pinfunction "dp_7") (pintype "passive"))
      (node (ref "DS2") (pin "7") (pinfunction "dp_7") (pintype "passive"))
      (node (ref "DS3") (pin "7") (pinfunction "dp_7") (pintype "passive"))
      (node (ref "DS4") (pin "7") (pinfunction "dp_7") (pintype "passive"))
      (node (ref "DS5") (pin "7") (pinfunction "dp_7") (pintype "passive"))
      (node (ref "DS6") (pin "7") (pinfunction "dp_7") (pintype "passive"))
      (node (ref "LD1") (pin "16") (pinfunction "H_16") (pintype "passive"))
      (node (ref "LED9") (pin "K") (pinfunction "2_K") (pintype "passive"))
      (node (ref "R25") (pin "1") (pinfunction "1_1") (pintype "passive"))
    )
    (net (code "28") (name "/DB_0") (class "Default")
      (node (ref "J6") (pin "1") (pinfunction "1_1") (pintype "passive"))
      (node (ref "LCD1") (pin "7") (pinfunction "DB0_7") (pintype "passive"))
      (node (ref "LCD2") (pin "7") (pinfunction "DB0_7") (pintype "power_in"))
      (node (ref "R17") (pin "2") (pinfunction "2_2") (pintype "passive"))
      (node (ref "U2") (pin "2") (pinfunction "A1_2") (pintype "passive"))
      (node (ref "U5") (pin "39") (pinfunction "P0.0/AD0_39") (pintype "passive"))
    )
    (net (code "29") (name "/DB_1") (class "Default")
      (node (ref "J6") (pin "2") (pinfunction "2_2") (pintype "passive"))
      (node (ref "LCD1") (pin "8") (pinfunction "DB1_8") (pintype "passive"))
      (node (ref "LCD2") (pin "8") (pinfunction "DB1_8") (pintype "power_in"))
      (node (ref "R16") (pin "2") (pinfunction "2_2") (pintype "passive"))
      (node (ref "U2") (pin "3") (pinfunction "A2_3") (pintype "passive"))
      (node (ref "U5") (pin "38") (pinfunction "P0.1/AD1_38") (pintype "passive"))
    )
    (net (code "30") (name "/DB_2") (class "Default")
      (node (ref "J6") (pin "3") (pinfunction "3_3") (pintype "passive"))
      (node (ref "LCD1") (pin "9") (pinfunction "DB2_9") (pintype "passive"))
      (node (ref "LCD2") (pin "9") (pinfunction "DB2_9") (pintype "power_in"))
      (node (ref "R15") (pin "2") (pinfunction "2_2") (pintype "passive"))
      (node (ref "U2") (pin "4") (pinfunction "A3_4") (pintype "passive"))
      (node (ref "U5") (pin "37") (pinfunction "P0.2/AD2_37") (pintype "passive"))
    )
    (net (code "31") (name "/DB_3") (class "Default")
      (node (ref "J6") (pin "4") (pinfunction "4_4") (pintype "passive"))
      (node (ref "LCD1") (pin "10") (pinfunction "DB3_10") (pintype "passive"))
      (node (ref "LCD2") (pin "10") (pinfunction "DB3_10") (pintype "power_in"))
      (node (ref "R14") (pin "2") (pinfunction "2_2") (pintype "passive"))
      (node (ref "U2") (pin "5") (pinfunction "A4_5") (pintype "passive"))
      (node (ref "U5") (pin "36") (pinfunction "P0.3/AD3_36") (pintype "passive"))
    )
    (net (code "32") (name "/DB_4") (class "Default")
      (node (ref "J6") (pin "5") (pinfunction "5_5") (pintype "passive"))
      (node (ref "LCD1") (pin "11") (pinfunction "DB4_11") (pintype "passive"))
      (node (ref "LCD2") (pin "11") (pinfunction "DB4_11") (pintype "power_in"))
      (node (ref "R13") (pin "2") (pinfunction "2_2") (pintype "passive"))
      (node (ref "U2") (pin "6") (pinfunction "A5_6") (pintype "passive"))
      (node (ref "U5") (pin "35") (pinfunction "P0.4/AD4_35") (pintype "passive"))
    )
    (net (code "33") (name "/DB_5") (class "Default")
      (node (ref "J6") (pin "6") (pinfunction "6_6") (pintype "passive"))
      (node (ref "LCD1") (pin "12") (pinfunction "DB5_12") (pintype "passive"))
      (node (ref "LCD2") (pin "12") (pinfunction "DB5_12") (pintype "power_in"))
      (node (ref "R12") (pin "2") (pinfunction "2_2") (pintype "passive"))
      (node (ref "U2") (pin "7") (pinfunction "A6_7") (pintype "passive"))
      (node (ref "U5") (pin "34") (pinfunction "P0.5/AD5_34") (pintype "passive"))
    )
    (net (code "34") (name "/DB_6") (class "Default")
      (node (ref "J6") (pin "7") (pinfunction "7_7") (pintype "passive"))
      (node (ref "LCD1") (pin "13") (pinfunction "DB6_13") (pintype "passive"))
      (node (ref "LCD2") (pin "13") (pinfunction "DB6_13") (pintype "power_in"))
      (node (ref "R11") (pin "2") (pinfunction "2_2") (pintype "passive"))
      (node (ref "U2") (pin "8") (pinfunction "A7_8") (pintype "passive"))
      (node (ref "U5") (pin "33") (pinfunction "P0.6/AD6_33") (pintype "passive"))
    )
    (net (code "35") (name "/DB_7") (class "Default")
      (node (ref "J6") (pin "8") (pinfunction "8_8") (pintype "passive"))
      (node (ref "LCD1") (pin "14") (pinfunction "DB7_14") (pintype "passive"))
      (node (ref "LCD2") (pin "14") (pinfunction "DB7_14") (pintype "power_in"))
      (node (ref "R10") (pin "2") (pinfunction "2_2") (pintype "passive"))
      (node (ref "U2") (pin "9") (pinfunction "A8_9") (pintype "passive"))
      (node (ref "U5") (pin "32") (pinfunction "P0.7/AD7_32") (pintype "passive"))
    )
    (net (code "36") (name "/DM") (class "Default")
      (node (ref "J3") (pin "2") (pinfunction "D-_2") (pintype "passive"))
      (node (ref "U1") (pin "7") (pinfunction "UD-_7") (pintype "passive"))
    )
    (net (code "37") (name "/DP") (class "Default")
      (node (ref "J3") (pin "3") (pinfunction "D+_3") (pintype "passive"))
      (node (ref "U1") (pin "6") (pinfunction "UD+_6") (pintype "passive"))
    )
    (net (code "38") (name "/ENLCD") (class "Default")
      (node (ref "J4") (pin "6") (pinfunction "6_6") (pintype "passive"))
      (node (ref "J8") (pin "2") (pinfunction "2_2") (pintype "passive"))
      (node (ref "U5") (pin "6") (pinfunction "P1.5_6") (pintype "passive"))
    )
    (net (code "39") (name "/ENLCD1") (class "Default")
      (node (ref "J8") (pin "1") (pinfunction "1_1") (pintype "passive"))
      (node (ref "LCD1") (pin "6") (pinfunction "E_6") (pintype "passive"))
      (node (ref "R72") (pin "2") (pintype "passive"))
    )
    (net (code "40") (name "/ENLCD2") (class "Default")
      (node (ref "J8") (pin "3") (pinfunction "3_3") (pintype "passive"))
      (node (ref "LCD2") (pin "6") (pinfunction "E_6") (pintype "power_in"))
      (node (ref "R68") (pin "1") (pintype "passive"))
    )
    (net (code "41") (name "/ENLED") (class "Default")
      (node (ref "J4") (pin "5") (pinfunction "5_5") (pintype "passive"))
      (node (ref "U3") (pin "4") (pinfunction "~{E1}_4") (pintype "passive"))
      (node (ref "U3") (pin "5") (pinfunction "~{E2}_5") (pintype "passive"))
      (node (ref "U4") (pin "5") (pinfunction "~{E2}_5") (pintype "passive"))
      (node (ref "U5") (pin "5") (pinfunction "P1.4_5") (pintype "passive"))
    )
    (net (code "42") (name "/IRD") (class "Default")
      (node (ref "J5") (pin "4") (pinfunction "4_4") (pintype "passive"))
      (node (ref "R70") (pin "2") (pinfunction "2_2") (pintype "passive"))
      (node (ref "U10") (pin "1") (pinfunction "OUT_1") (pintype "output"))
      (node (ref "U5") (pin "13") (pinfunction "P3.3/~{INT1}_13") (pintype "passive"))
    )
    (net (code "43") (name "/KeyIn1") (class "Default")
      (node (ref "J7") (pin "4") (pinfunction "4_4") (pintype "passive"))
      (node (ref "K1") (pin "1") (pinfunction "1_1") (pintype "passive"))
      (node (ref "K13") (pin "1") (pinfunction "1_1") (pintype "passive"))
      (node (ref "K5") (pin "1") (pinfunction "1_1") (pintype "passive"))
      (node (ref "K9") (pin "1") (pinfunction "1_1") (pintype "passive"))
      (node (ref "R1") (pin "1") (pinfunction "1_1") (pintype "passive"))
      (node (ref "U5") (pin "25") (pinfunction "P2.4/A12_25") (pintype "passive"))
    )
    (net (code "44") (name "/KeyIn2") (class "Default")
      (node (ref "J7") (pin "3") (pinfunction "3_3") (pintype "passive"))
      (node (ref "K10") (pin "1") (pinfunction "1_1") (pintype "passive"))
      (node (ref "K14") (pin "1") (pinfunction "1_1") (pintype "passive"))
      (node (ref "K2") (pin "1") (pinfunction "1_1") (pintype "passive"))
      (node (ref "K6") (pin "1") (pinfunction "1_1") (pintype "passive"))
      (node (ref "R2") (pin "1") (pinfunction "1_1") (pintype "passive"))
      (node (ref "U5") (pin "26") (pinfunction "P2.5/A13_26") (pintype "passive"))
    )
    (net (code "45") (name "/KeyIn3") (class "Default")
      (node (ref "J7") (pin "2") (pinfunction "2_2") (pintype "passive"))
      (node (ref "K11") (pin "1") (pinfunction "1_1") (pintype "passive"))
      (node (ref "K15") (pin "1") (pinfunction "1_1") (pintype "passive"))
      (node (ref "K3") (pin "1") (pinfunction "1_1") (pintype "passive"))
      (node (ref "K7") (pin "1") (pinfunction "1_1") (pintype "passive"))
      (node (ref "R3") (pin "1") (pinfunction "1_1") (pintype "passive"))
      (node (ref "U5") (pin "27") (pinfunction "P2.6/A14_27") (pintype "passive"))
    )
    (net (code "46") (name "/KeyIn4") (class "Default")
      (node (ref "J7") (pin "1") (pinfunction "1_1") (pintype "passive"))
      (node (ref "K12") (pin "1") (pinfunction "1_1") (pintype "passive"))
      (node (ref "K16") (pin "1") (pinfunction "1_1") (pintype "passive"))
      (node (ref "K4") (pin "1") (pinfunction "1_1") (pintype "passive"))
      (node (ref "K8") (pin "1") (pinfunction "1_1") (pintype "passive"))
      (node (ref "R4") (pin "1") (pinfunction "1_1") (pintype "passive"))
      (node (ref "U5") (pin "28") (pinfunction "P2.7/A15_28") (pintype "passive"))
    )
    (net (code "47") (name "/KeyOut1") (class "Default")
      (node (ref "J7") (pin "5") (pinfunction "5_5") (pintype "passive"))
      (node (ref "K1") (pin "2") (pinfunction "2_2") (pintype "passive"))
      (node (ref "K2") (pin "2") (pinfunction "2_2") (pintype "passive"))
      (node (ref "K3") (pin "2") (pinfunction "2_2") (pintype "passive"))
      (node (ref "K4") (pin "2") (pinfunction "2_2") (pintype "passive"))
      (node (ref "U5") (pin "24") (pinfunction "P2.3/A11_24") (pintype "passive"))
    )
    (net (code "48") (name "/KeyOut2") (class "Default")
      (node (ref "J7") (pin "6") (pinfunction "6_6") (pintype "passive"))
      (node (ref "K5") (pin "2") (pinfunction "2_2") (pintype "passive"))
      (node (ref "K6") (pin "2") (pinfunction "2_2") (pintype "passive"))
      (node (ref "K7") (pin "2") (pinfunction "2_2") (pintype "passive"))
      (node (ref "K8") (pin "2") (pinfunction "2_2") (pintype "passive"))
      (node (ref "U5") (pin "23") (pinfunction "P2.2/A10_23") (pintype "passive"))
    )
    (net (code "49") (name "/KeyOut3") (class "Default")
      (node (ref "J7") (pin "7") (pinfunction "7_7") (pintype "passive"))
      (node (ref "K10") (pin "2") (pinfunction "2_2") (pintype "passive"))
      (node (ref "K11") (pin "2") (pinfunction "2_2") (pintype "passive"))
      (node (ref "K12") (pin "2") (pinfunction "2_2") (pintype "passive"))
      (node (ref "K9") (pin "2") (pinfunction "2_2") (pintype "passive"))
      (node (ref "U5") (pin "22") (pinfunction "P2.1/A9_22") (pintype "passive"))
    )
    (net (code "50") (name "/KeyOut4") (class "Default")
      (node (ref "J7") (pin "8") (pinfunction "8_8") (pintype "passive"))
      (node (ref "K13") (pin "2") (pinfunction "2_2") (pintype "passive"))
      (node (ref "K14") (pin "2") (pinfunction "2_2") (pintype "passive"))
      (node (ref "K15") (pin "2") (pinfunction "2_2") (pintype "passive"))
      (node (ref "K16") (pin "2") (pinfunction "2_2") (pintype "passive"))
      (node (ref "U5") (pin "21") (pinfunction "P2.0/A8_21") (pintype "passive"))
    )
    (net (code "51") (name "/LEDC0") (class "Default")
      (node (ref "R40") (pin "1") (pinfunction "1_1") (pintype "passive"))
      (node (ref "U4") (pin "15") (pinfunction "~{Y0}_15") (pintype "passive"))
    )
    (net (code "52") (name "/LEDC1") (class "Default")
      (node (ref "R41") (pin "1") (pinfunction "1_1") (pintype "passive"))
      (node (ref "U4") (pin "14") (pinfunction "~{Y1}_14") (pintype "passive"))
    )
    (net (code "53") (name "/LEDC2") (class "Default")
      (node (ref "R42") (pin "1") (pinfunction "1_1") (pintype "passive"))
      (node (ref "U4") (pin "13") (pinfunction "~{Y2}_13") (pintype "passive"))
    )
    (net (code "54") (name "/LEDC3") (class "Default")
      (node (ref "R43") (pin "1") (pinfunction "1_1") (pintype "passive"))
      (node (ref "U4") (pin "12") (pinfunction "~{Y3}_12") (pintype "passive"))
    )
    (net (code "55") (name "/LEDC4") (class "Default")
      (node (ref "R48") (pin "1") (pinfunction "1_1") (pintype "passive"))
      (node (ref "U4") (pin "11") (pinfunction "~{Y4}_11") (pintype "passive"))
    )
    (net (code "56") (name "/LEDC5") (class "Default")
      (node (ref "R49") (pin "1") (pinfunction "1_1") (pintype "passive"))
      (node (ref "U4") (pin "10") (pinfunction "~{Y5}_10") (pintype "passive"))
    )
    (net (code "57") (name "/LEDC6") (class "Default")
      (node (ref "R50") (pin "1") (pinfunction "1_1") (pintype "passive"))
      (node (ref "U4") (pin "9") (pinfunction "~{Y6}_9") (pintype "passive"))
    )
    (net (code "58") (name "/LEDC7") (class "Default")
      (node (ref "R51") (pin "1") (pinfunction "1_1") (pintype "passive"))
      (node (ref "U4") (pin "7") (pinfunction "~{Y7}_7") (pintype "passive"))
    )
    (net (code "59") (name "/LEDS0") (class "Default")
      (node (ref "R46") (pin "1") (pinfunction "1_1") (pintype "passive"))
      (node (ref "U3") (pin "15") (pinfunction "~{Y0}_15") (pintype "passive"))
    )
    (net (code "60") (name "/LEDS1") (class "Default")
      (node (ref "R45") (pin "1") (pinfunction "1_1") (pintype "passive"))
      (node (ref "U3") (pin "14") (pinfunction "~{Y1}_14") (pintype "passive"))
    )
    (net (code "61") (name "/LEDS2") (class "Default")
      (node (ref "R44") (pin "1") (pinfunction "1_1") (pintype "passive"))
      (node (ref "U3") (pin "13") (pinfunction "~{Y2}_13") (pintype "passive"))
    )
    (net (code "62") (name "/LEDS3") (class "Default")
      (node (ref "R39") (pin "1") (pinfunction "1_1") (pintype "passive"))
      (node (ref "U3") (pin "12") (pinfunction "~{Y3}_12") (pintype "passive"))
    )
    (net (code "63") (name "/LEDS4") (class "Default")
      (node (ref "R38") (pin "1") (pinfunction "1_1") (pintype "passive"))
      (node (ref "U3") (pin "11") (pinfunction "~{Y4}_11") (pintype "passive"))
    )
    (net (code "64") (name "/LEDS5") (class "Default")
      (node (ref "R37") (pin "1") (pinfunction "1_1") (pintype "passive"))
      (node (ref "U3") (pin "10") (pinfunction "~{Y5}_10") (pintype "passive"))
    )
    (net (code "65") (name "/LEDS6") (class "Default")
      (node (ref "R47") (pin "2") (pinfunction "2_2") (pintype "passive"))
      (node (ref "U3") (pin "9") (pinfunction "~{Y6}_9") (pintype "passive"))
    )
    (net (code "66") (name "/MC0") (class "Default")
      (node (ref "J13") (pin "3") (pinfunction "3_3") (pintype "passive"))
      (node (ref "R53") (pin "1") (pinfunction "1_1") (pintype "passive"))
    )
    (net (code "67") (name "/MC1") (class "Default")
      (node (ref "J14") (pin "3") (pinfunction "3_3") (pintype "passive"))
      (node (ref "R54") (pin "1") (pinfunction "1_1") (pintype "passive"))
    )
    (net (code "68") (name "/MC2") (class "Default")
      (node (ref "J15") (pin "3") (pinfunction "3_3") (pintype "passive"))
      (node (ref "R55") (pin "1") (pinfunction "1_1") (pintype "passive"))
    )
    (net (code "69") (name "/MC3") (class "Default")
      (node (ref "J16") (pin "3") (pinfunction "3_3") (pintype "passive"))
      (node (ref "R56") (pin "1") (pinfunction "1_1") (pintype "passive"))
    )
    (net (code "70") (name "/P1.0") (class "Default")
      (node (ref "J13") (pin "2") (pinfunction "2_2") (pintype "passive"))
      (node (ref "J4") (pin "1") (pinfunction "1_1") (pintype "passive"))
      (node (ref "U5") (pin "1") (pinfunction "P1.0/T2_1") (pintype "passive"))
    )
    (net (code "71") (name "/P1.1") (class "Default")
      (node (ref "J14") (pin "2") (pinfunction "2_2") (pintype "passive"))
      (node (ref "J4") (pin "2") (pinfunction "2_2") (pintype "passive"))
      (node (ref "U5") (pin "2") (pinfunction "P1.1/T2EX_2") (pintype "passive"))
    )
    (net (code "72") (name "/P1.2") (class "Default")
      (node (ref "J15") (pin "2") (pinfunction "2_2") (pintype "passive"))
      (node (ref "J4") (pin "3") (pinfunction "3_3") (pintype "passive"))
      (node (ref "U5") (pin "3") (pinfunction "P1.2_3") (pintype "passive"))
    )
    (net (code "73") (name "/P1.3") (class "Default")
      (node (ref "J16") (pin "2") (pinfunction "2_2") (pintype "passive"))
      (node (ref "J4") (pin "4") (pinfunction "4_4") (pintype "passive"))
      (node (ref "U5") (pin "4") (pinfunction "P1.3_4") (pintype "passive"))
    )
    (net (code "74") (name "/RST") (class "Default")
      (node (ref "C11") (pin "1") (pinfunction "1_1") (pintype "passive"))
      (node (ref "R31") (pin "1") (pinfunction "1_1") (pintype "passive"))
      (node (ref "R60") (pin "2") (pinfunction "2_2") (pintype "passive"))
      (node (ref "U5") (pin "9") (pinfunction "RST_9") (pintype "passive"))
    )
    (net (code "75") (name "/RXD") (class "Default")
      (node (ref "J2") (pin "2") (pinfunction "2_2") (pintype "passive"))
      (node (ref "J5") (pin "1") (pinfunction "1_1") (pintype "passive"))
      (node (ref "U5") (pin "10") (pinfunction "P3.0/RXD_10") (pintype "passive"))
    )
    (net (code "76") (name "/S1302") (class "Default")
      (node (ref "J4") (pin "8") (pinfunction "8_8") (pintype "passive"))
      (node (ref "R32") (pin "1") (pinfunction "1_1") (pintype "passive"))
      (node (ref "U5") (pin "8") (pinfunction "P1.7_8") (pintype "passive"))
      (node (ref "U8") (pin "5") (pinfunction "CE_5") (pintype "passive"))
    )
    (net (code "77") (name "/SCK") (class "Default")
      (node (ref "J5") (pin "6") (pinfunction "6_6") (pintype "passive"))
      (node (ref "R9") (pin "1") (pinfunction "1_1") (pintype "passive"))
      (node (ref "U5") (pin "15") (pinfunction "P3.5/T1_15") (pintype "passive"))
      (node (ref "U8") (pin "7") (pinfunction "SCLK_7") (pintype "passive"))
    )
    (net (code "78") (name "/SCL") (class "Default")
      (node (ref "J5") (pin "8") (pinfunction "8_8") (pintype "passive"))
      (node (ref "R63") (pin "1") (pinfunction "1_1") (pintype "passive"))
      (node (ref "U5") (pin "17") (pinfunction "P3.7/~{RD}_17") (pintype "passive"))
      (node (ref "U6") (pin "10") (pinfunction "SCL_10") (pintype "passive"))
      (node (ref "U7") (pin "6") (pinfunction "SCL_6") (pintype "passive"))
    )
    (net (code "79") (name "/SDA") (class "Default")
      (node (ref "J5") (pin "7") (pinfunction "7_7") (pintype "passive"))
      (node (ref "R64") (pin "1") (pinfunction "1_1") (pintype "passive"))
      (node (ref "U5") (pin "16") (pinfunction "P3.6/~{WR}_16") (pintype "passive"))
      (node (ref "U6") (pin "9") (pinfunction "SDA_9") (pintype "passive"))
      (node (ref "U7") (pin "5") (pinfunction "SDA_5") (pintype "passive"))
    )
    (net (code "80") (name "/SIO") (class "Default")
      (node (ref "J5") (pin "5") (pinfunction "5_5") (pintype "passive"))
      (node (ref "R26") (pin "1") (pinfunction "1_1") (pintype "passive"))
      (node (ref "U5") (pin "14") (pinfunction "P3.4/T0_14") (pintype "passive"))
      (node (ref "U8") (pin "6") (pinfunction "I/O_6") (pintype "passive"))
    )
    (net (code "81") (name "/TXD") (class "Default")
      (node (ref "J1") (pin "2") (pinfunction "2_2") (pintype "passive"))
      (node (ref "J5") (pin "2") (pinfunction "2_2") (pintype "passive"))
      (node (ref "U5") (pin "11") (pinfunction "P3.1/TXD_11") (pintype "passive"))
    )
    (net (code "82") (name "/USB-RX") (class "Default")
      (node (ref "D5") (pin "A") (pinfunction "1_A") (pintype "passive"))
      (node (ref "J2") (pin "1") (pinfunction "1_1") (pintype "passive"))
    )
    (net (code "83") (name "/USB-TX") (class "Default")
      (node (ref "J1") (pin "1") (pinfunction "1_1") (pintype "passive"))
      (node (ref "U1") (pin "4") (pinfunction "RXD_4") (pintype "input"))
    )
    (net (code "84") (name "/VRout") (class "Default")
      (node (ref "J17") (pin "5") (pinfunction "5_5") (pintype "passive"))
      (node (ref "R62") (pin "2") (pinfunction "2_2") (pintype "passive"))
    )
    (net (code "85") (name "/Vref") (class "Default")
      (node (ref "C1") (pin "2") (pinfunction "2_2") (pintype "passive"))
      (node (ref "J17") (pin "4") (pinfunction "4_4") (pintype "passive"))
      (node (ref "U6") (pin "14") (pinfunction "Vref_14") (pintype "passive"))
    )
    (net (code "86") (name "GND") (class "Default")
      (node (ref "BZ1") (pin "2") (pinfunction "2_2") (pintype "passive"))
      (node (ref "C1") (pin "1") (pinfunction "1_1") (pintype "passive"))
      (node (ref "C10") (pin "2") (pinfunction "2_2") (pintype "passive"))
      (node (ref "C12") (pin "1") (pinfunction "1_1") (pintype "passive"))
      (node (ref "C13") (pin "1") (pinfunction "1_1") (pintype "passive"))
      (node (ref "C14") (pin "2") (pinfunction "2_2") (pintype "passive"))
      (node (ref "C15") (pin "2") (pinfunction "2_2") (pintype "passive"))
      (node (ref "C16") (pin "2") (pinfunction "2_2") (pintype "passive"))
      (node (ref "C18") (pin "2") (pinfunction "2_2") (pintype "passive"))
      (node (ref "C19") (pin "2") (pinfunction "2_2") (pintype "passive"))
      (node (ref "C2") (pin "1") (pinfunction "1_1") (pintype "passive"))
      (node (ref "C20") (pin "1") (pinfunction "1_1") (pintype "passive"))
      (node (ref "C21") (pin "2") (pinfunction "2_2") (pintype "passive"))
      (node (ref "C22") (pin "2") (pinfunction "2_2") (pintype "passive"))
      (node (ref "C23") (pin "2") (pinfunction "2_2") (pintype "passive"))
      (node (ref "C24") (pin "2") (pinfunction "2_2") (pintype "passive"))
      (node (ref "C25") (pin "2") (pinfunction "2_2") (pintype "passive"))
      (node (ref "C26") (pin "1") (pinfunction "1_1") (pintype "passive"))
      (node (ref "C28") (pin "1") (pinfunction "1_1") (pintype "passive"))
      (node (ref "C29") (pin "1") (pinfunction "1_1") (pintype "passive"))
      (node (ref "C3") (pin "1") (pinfunction "1_1") (pintype "passive"))
      (node (ref "C30") (pin "2") (pinfunction "2_2") (pintype "passive"))
      (node (ref "C4") (pin "1") (pinfunction "1_1") (pintype "passive"))
      (node (ref "C7") (pin "1") (pinfunction "1_1") (pintype "passive"))
      (node (ref "C8") (pin "2") (pinfunction "2_2") (pintype "passive"))
      (node (ref "C9") (pin "2") (pinfunction "2_2") (pintype "passive"))
      (node (ref "D4") (pin "A") (pinfunction "1_A") (pintype "passive"))
      (node (ref "J17") (pin "7") (pinfunction "7_7") (pintype "passive"))
      (node (ref "J17") (pin "9") (pinfunction "9_9") (pintype "passive"))
      (node (ref "J3") (pin "4") (pinfunction "GND_4") (pintype "passive"))
      (node (ref "J3") (pin "5") (pinfunction "S_5") (pintype "passive"))
      (node (ref "J3") (pin "6") (pinfunction "S_6") (pintype "passive"))
      (node (ref "LCD1") (pin "1") (pinfunction "GND_1") (pintype "passive"))
      (node (ref "LCD1") (pin "16") (pinfunction "BG_GND_16") (pintype "passive"))
      (node (ref "LCD2") (pin "1") (pinfunction "GND_1") (pintype "power_in"))
      (node (ref "LCD2") (pin "20") (pinfunction "LED-K_20") (pintype "power_in"))
      (node (ref "Q2") (pin "C") (pinfunction "C_C") (pintype "passive"))
      (node (ref "Q3") (pin "C") (pinfunction "C_C") (pintype "passive"))
      (node (ref "Q4") (pin "C") (pinfunction "C_C") (pintype "passive"))
      (node (ref "Q5") (pin "C") (pinfunction "C_C") (pintype "passive"))
      (node (ref "R31") (pin "2") (pinfunction "2_2") (pintype "passive"))
      (node (ref "R34") (pin "2") (pinfunction "2_2") (pintype "passive"))
      (node (ref "R35") (pin "2") (pinfunction "2_2") (pintype "passive"))
      (node (ref "R62") (pin "3") (pinfunction "3_3") (pintype "passive"))
      (node (ref "R67") (pin "1") (pintype "passive"))
      (node (ref "R68") (pin "2") (pintype "passive"))
      (node (ref "R72") (pin "1") (pintype "passive"))
      (node (ref "TP4") (pin "1") (pintype "passive"))
      (node (ref "TP5") (pin "1") (pintype "passive"))
      (node (ref "U1") (pin "8") (pinfunction "GND_8") (pintype "power_in"))
      (node (ref "U10") (pin "2") (pinfunction "GND_2") (pintype "power_in"))
      (node (ref "U11") (pin "5") (pinfunction "GND_5") (pintype "power_in"))
      (node (ref "U12") (pin "3") (pinfunction "ANODE_3") (pintype "power_in"))
      (node (ref "U2") (pin "10") (pinfunction "GND_10") (pintype "passive"))
      (node (ref "U2") (pin "19") (pinfunction "~{OE}_19") (pintype "passive"))
      (node (ref "U3") (pin "8") (pinfunction "GND_8") (pintype "passive"))
      (node (ref "U4") (pin "8") (pinfunction "GND_8") (pintype "passive"))
      (node (ref "U5") (pin "20") (pinfunction "GND_20") (pintype "passive"))
      (node (ref "U6") (pin "12") (pinfunction "EXT_12") (pintype "passive"))
      (node (ref "U6") (pin "13") (pinfunction "AGND_13") (pintype "passive"))
      (node (ref "U6") (pin "5") (pinfunction "A0_5") (pintype "passive"))
      (node (ref "U6") (pin "6") (pinfunction "A1_6") (pintype "passive"))
      (node (ref "U6") (pin "7") (pinfunction "A2_7") (pintype "passive"))
      (node (ref "U6") (pin "8") (pinfunction "VSS_8") (pintype "passive"))
      (node (ref "U7") (pin "1") (pinfunction "A0_1") (pintype "passive"))
      (node (ref "U7") (pin "2") (pinfunction "A1_2") (pintype "passive"))
      (node (ref "U7") (pin "3") (pinfunction "A2_3") (pintype "passive"))
      (node (ref "U7") (pin "4") (pinfunction "GND_4") (pintype "passive"))
      (node (ref "U7") (pin "7") (pinfunction "WP_7") (pintype "passive"))
      (node (ref "U8") (pin "4") (pinfunction "GND_4") (pintype "passive"))
      (node (ref "U9") (pin "1") (pinfunction "GND_1") (pintype "passive"))
    )
    (net (code "87") (name "Net-(D1-2)") (class "Default")
      (node (ref "C2") (pin "2") (pinfunction "2_2") (pintype "passive"))
      (node (ref "D1") (pin "K") (pinfunction "2_K") (pintype "passive"))
      (node (ref "U8") (pin "8") (pinfunction "Vcc1_8") (pintype "passive"))
    )
    (net (code "88") (name "Net-(D4-2)") (class "Default")
      (node (ref "BZ1") (pin "1") (pinfunction "1_1") (pintype "passive"))
      (node (ref "D4") (pin "K") (pinfunction "2_K") (pintype "passive"))
      (node (ref "R7") (pin "2") (pinfunction "2_2") (pintype "passive"))
    )
    (net (code "89") (name "Net-(D5-2)") (class "Default")
      (node (ref "D5") (pin "K") (pinfunction "2_K") (pintype "passive"))
      (node (ref "U1") (pin "3") (pinfunction "TXD_3") (pintype "output"))
    )
    (net (code "90") (name "Net-(DS1-com-Pad1)") (class "Default")
      (node (ref "DS1") (pin "1") (pinfunction "com_1") (pintype "passive"))
      (node (ref "DS1") (pin "6") (pinfunction "com_6") (pintype "passive"))
      (node (ref "Q17") (pin "C") (pinfunction "C_C") (pintype "passive"))
    )
    (net (code "91") (name "Net-(DS2-com-Pad1)") (class "Default")
      (node (ref "DS2") (pin "1") (pinfunction "com_1") (pintype "passive"))
      (node (ref "DS2") (pin "6") (pinfunction "com_6") (pintype "passive"))
      (node (ref "Q15") (pin "C") (pinfunction "C_C") (pintype "passive"))
    )
    (net (code "92") (name "Net-(DS3-com-Pad1)") (class "Default")
      (node (ref "DS3") (pin "1") (pinfunction "com_1") (pintype "passive"))
      (node (ref "DS3") (pin "6") (pinfunction "com_6") (pintype "passive"))
      (node (ref "Q14") (pin "C") (pinfunction "C_C") (pintype "passive"))
    )
    (net (code "93") (name "Net-(DS4-com-Pad1)") (class "Default")
      (node (ref "DS4") (pin "1") (pinfunction "com_1") (pintype "passive"))
      (node (ref "DS4") (pin "6") (pinfunction "com_6") (pintype "passive"))
      (node (ref "Q9") (pin "C") (pinfunction "C_C") (pintype "passive"))
    )
    (net (code "94") (name "Net-(DS5-com-Pad1)") (class "Default")
      (node (ref "DS5") (pin "1") (pinfunction "com_1") (pintype "passive"))
      (node (ref "DS5") (pin "6") (pinfunction "com_6") (pintype "passive"))
      (node (ref "Q8") (pin "C") (pinfunction "C_C") (pintype "passive"))
    )
    (net (code "95") (name "Net-(DS6-com-Pad1)") (class "Default")
      (node (ref "DS6") (pin "1") (pinfunction "com_1") (pintype "passive"))
      (node (ref "DS6") (pin "6") (pinfunction "com_6") (pintype "passive"))
      (node (ref "Q7") (pin "C") (pinfunction "C_C") (pintype "passive"))
    )
    (net (code "96") (name "Net-(J3-VCC)") (class "Default")
      (node (ref "F1") (pin "1") (pinfunction "1_1") (pintype "passive"))
      (node (ref "J3") (pin "1") (pinfunction "VCC_1") (pintype "passive"))
    )
    (net (code "97") (name "Net-(J12-Pad2)") (class "Default")
      (node (ref "J12") (pin "2") (pinfunction "2_2") (pintype "passive"))
      (node (ref "Q2") (pin "E") (pinfunction "E_E") (pintype "passive"))
    )
    (net (code "98") (name "Net-(J12-Pad3)") (class "Default")
      (node (ref "J12") (pin "3") (pinfunction "3_3") (pintype "passive"))
      (node (ref "Q3") (pin "E") (pinfunction "E_E") (pintype "passive"))
    )
    (net (code "99") (name "Net-(J12-Pad4)") (class "Default")
      (node (ref "J12") (pin "4") (pinfunction "4_4") (pintype "passive"))
      (node (ref "Q4") (pin "E") (pinfunction "E_E") (pintype "passive"))
    )
    (net (code "100") (name "Net-(J12-Pad5)") (class "Default")
      (node (ref "J12") (pin "5") (pinfunction "5_5") (pintype "passive"))
      (node (ref "Q5") (pin "E") (pinfunction "E_E") (pintype "passive"))
    )
    (net (code "101") (name "Net-(K17-Pad1)") (class "Default")
      (node (ref "K17") (pin "1") (pinfunction "1_1") (pintype "passive"))
      (node (ref "R60") (pin "1") (pinfunction "1_1") (pintype "passive"))
    )
    (net (code "102") (name "Net-(LCD1-VO)") (class "Default")
      (node (ref "LCD1") (pin "3") (pinfunction "VO_3") (pintype "passive"))
      (node (ref "R67") (pin "2") (pintype "passive"))
    )
    (net (code "103") (name "Net-(LD1-1)") (class "Default")
      (node (ref "LD1") (pin "9") (pinfunction "1_9") (pintype "passive"))
      (node (ref "Q10") (pin "C") (pinfunction "C_C") (pintype "passive"))
    )
    (net (code "104") (name "Net-(LD1-2)") (class "Default")
      (node (ref "LD1") (pin "14") (pinfunction "2_14") (pintype "passive"))
      (node (ref "Q11") (pin "C") (pinfunction "C_C") (pintype "passive"))
    )
    (net (code "105") (name "Net-(LD1-3)") (class "Default")
      (node (ref "LD1") (pin "8") (pinfunction "3_8") (pintype "passive"))
      (node (ref "Q12") (pin "C") (pinfunction "C_C") (pintype "passive"))
    )
    (net (code "106") (name "Net-(LD1-4)") (class "Default")
      (node (ref "LD1") (pin "12") (pinfunction "4_12") (pintype "passive"))
      (node (ref "Q13") (pin "C") (pinfunction "C_C") (pintype "passive"))
    )
    (net (code "107") (name "Net-(LD1-5)") (class "Default")
      (node (ref "LD1") (pin "1") (pinfunction "5_1") (pintype "passive"))
      (node (ref "Q18") (pin "C") (pinfunction "C_C") (pintype "passive"))
    )
    (net (code "108") (name "Net-(LD1-6)") (class "Default")
      (node (ref "LD1") (pin "7") (pinfunction "6_7") (pintype "passive"))
      (node (ref "Q19") (pin "C") (pinfunction "C_C") (pintype "passive"))
    )
    (net (code "109") (name "Net-(LD1-7)") (class "Default")
      (node (ref "LD1") (pin "2") (pinfunction "7_2") (pintype "passive"))
      (node (ref "Q20") (pin "C") (pinfunction "C_C") (pintype "passive"))
    )
    (net (code "110") (name "Net-(LD1-8)") (class "Default")
      (node (ref "LD1") (pin "5") (pinfunction "8_5") (pintype "passive"))
      (node (ref "Q21") (pin "C") (pinfunction "C_C") (pintype "passive"))
    )
    (net (code "111") (name "Net-(LED1-2)") (class "Default")
      (node (ref "LED1") (pin "K") (pinfunction "2_K") (pintype "passive"))
      (node (ref "R34") (pin "1") (pinfunction "1_1") (pintype "passive"))
    )
    (net (code "112") (name "Net-(LED2-1)") (class "Default")
      (node (ref "LED2") (pin "A") (pinfunction "1_A") (pintype "passive"))
      (node (ref "LED3") (pin "A") (pinfunction "1_A") (pintype "passive"))
      (node (ref "LED4") (pin "A") (pinfunction "1_A") (pintype "passive"))
      (node (ref "LED5") (pin "A") (pinfunction "1_A") (pintype "passive"))
      (node (ref "LED6") (pin "A") (pinfunction "1_A") (pintype "passive"))
      (node (ref "LED7") (pin "A") (pinfunction "1_A") (pintype "passive"))
      (node (ref "LED8") (pin "A") (pinfunction "1_A") (pintype "passive"))
      (node (ref "LED9") (pin "A") (pinfunction "1_A") (pintype "passive"))
      (node (ref "Q16") (pin "C") (pinfunction "C_C") (pintype "passive"))
    )
    (net (code "113") (name "Net-(LED10-2)") (class "Default")
      (node (ref "LED10") (pin "K") (pinfunction "2_K") (pintype "passive"))
      (node (ref "R35") (pin "1") (pinfunction "1_1") (pintype "passive"))
    )
    (net (code "114") (name "Net-(Q2-PadB)") (class "Default")
      (node (ref "Q2") (pin "B") (pinfunction "B_B") (pintype "passive"))
      (node (ref "R53") (pin "2") (pinfunction "2_2") (pintype "passive"))
    )
    (net (code "115") (name "Net-(Q3-PadB)") (class "Default")
      (node (ref "Q3") (pin "B") (pinfunction "B_B") (pintype "passive"))
      (node (ref "R54") (pin "2") (pinfunction "2_2") (pintype "passive"))
    )
    (net (code "116") (name "Net-(Q4-PadB)") (class "Default")
      (node (ref "Q4") (pin "B") (pinfunction "B_B") (pintype "passive"))
      (node (ref "R55") (pin "2") (pinfunction "2_2") (pintype "passive"))
    )
    (net (code "117") (name "Net-(Q5-PadB)") (class "Default")
      (node (ref "Q5") (pin "B") (pinfunction "B_B") (pintype "passive"))
      (node (ref "R56") (pin "2") (pinfunction "2_2") (pintype "passive"))
    )
    (net (code "118") (name "Net-(Q7-PadB)") (class "Default")
      (node (ref "Q7") (pin "B") (pinfunction "B_B") (pintype "passive"))
      (node (ref "R37") (pin "2") (pinfunction "2_2") (pintype "passive"))
    )
    (net (code "119") (name "Net-(Q8-PadB)") (class "Default")
      (node (ref "Q8") (pin "B") (pinfunction "B_B") (pintype "passive"))
      (node (ref "R38") (pin "2") (pinfunction "2_2") (pintype "passive"))
    )
    (net (code "120") (name "Net-(Q9-PadB)") (class "Default")
      (node (ref "Q9") (pin "B") (pinfunction "B_B") (pintype "passive"))
      (node (ref "R39") (pin "2") (pinfunction "2_2") (pintype "passive"))
    )
    (net (code "121") (name "Net-(Q10-PadB)") (class "Default")
      (node (ref "Q10") (pin "B") (pinfunction "B_B") (pintype "passive"))
      (node (ref "R40") (pin "2") (pinfunction "2_2") (pintype "passive"))
    )
    (net (code "122") (name "Net-(Q11-PadB)") (class "Default")
      (node (ref "Q11") (pin "B") (pinfunction "B_B") (pintype "passive"))
      (node (ref "R41") (pin "2") (pinfunction "2_2") (pintype "passive"))
    )
    (net (code "123") (name "Net-(Q12-PadB)") (class "Default")
      (node (ref "Q12") (pin "B") (pinfunction "B_B") (pintype "passive"))
      (node (ref "R42") (pin "2") (pinfunction "2_2") (pintype "passive"))
    )
    (net (code "124") (name "Net-(Q13-PadB)") (class "Default")
      (node (ref "Q13") (pin "B") (pinfunction "B_B") (pintype "passive"))
      (node (ref "R43") (pin "2") (pinfunction "2_2") (pintype "passive"))
    )
    (net (code "125") (name "Net-(Q14-PadB)") (class "Default")
      (node (ref "Q14") (pin "B") (pinfunction "B_B") (pintype "passive"))
      (node (ref "R44") (pin "2") (pinfunction "2_2") (pintype "passive"))
    )
    (net (code "126") (name "Net-(Q15-PadB)") (class "Default")
      (node (ref "Q15") (pin "B") (pinfunction "B_B") (pintype "passive"))
      (node (ref "R45") (pin "2") (pinfunction "2_2") (pintype "passive"))
    )
    (net (code "127") (name "Net-(Q16-PadB)") (class "Default")
      (node (ref "Q16") (pin "B") (pinfunction "B_B") (pintype "passive"))
      (node (ref "R47") (pin "1") (pinfunction "1_1") (pintype "passive"))
    )
    (net (code "128") (name "Net-(Q17-PadB)") (class "Default")
      (node (ref "Q17") (pin "B") (pinfunction "B_B") (pintype "passive"))
      (node (ref "R46") (pin "2") (pinfunction "2_2") (pintype "passive"))
    )
    (net (code "129") (name "Net-(Q18-PadB)") (class "Default")
      (node (ref "Q18") (pin "B") (pinfunction "B_B") (pintype "passive"))
      (node (ref "R48") (pin "2") (pinfunction "2_2") (pintype "passive"))
    )
    (net (code "130") (name "Net-(Q19-PadB)") (class "Default")
      (node (ref "Q19") (pin "B") (pinfunction "B_B") (pintype "passive"))
      (node (ref "R49") (pin "2") (pinfunction "2_2") (pintype "passive"))
    )
    (net (code "131") (name "Net-(Q20-PadB)") (class "Default")
      (node (ref "Q20") (pin "B") (pinfunction "B_B") (pintype "passive"))
      (node (ref "R50") (pin "2") (pinfunction "2_2") (pintype "passive"))
    )
    (net (code "132") (name "Net-(Q21-PadB)") (class "Default")
      (node (ref "Q21") (pin "B") (pinfunction "B_B") (pintype "passive"))
      (node (ref "R51") (pin "2") (pinfunction "2_2") (pintype "passive"))
    )
    (net (code "133") (name "Net-(Q22-PadB)") (class "Default")
      (node (ref "Q22") (pin "B") (pinfunction "B_B") (pintype "passive"))
      (node (ref "R52") (pin "2") (pinfunction "2_2") (pintype "passive"))
    )
    (net (code "134") (name "Net-(Q22-PadC)") (class "Default")
      (node (ref "Q22") (pin "C") (pinfunction "C_C") (pintype "passive"))
      (node (ref "R7") (pin "1") (pinfunction "1_1") (pintype "passive"))
    )
    (net (code "135") (name "Net-(U1-V3)") (class "Default")
      (node (ref "C3") (pin "2") (pinfunction "2_2") (pintype "passive"))
      (node (ref "U1") (pin "5") (pinfunction "V3_5") (pintype "power_in"))
    )
    (net (code "136") (name "Net-(U1-XI)") (class "Default")
      (node (ref "C12") (pin "2") (pinfunction "2_2") (pintype "passive"))
      (node (ref "U1") (pin "9") (pinfunction "XI_9") (pintype "input"))
      (node (ref "Y1") (pin "1") (pinfunction "1_1") (pintype "passive"))
    )
    (net (code "137") (name "Net-(U1-XO)") (class "Default")
      (node (ref "C13") (pin "2") (pinfunction "2_2") (pintype "passive"))
      (node (ref "U1") (pin "10") (pinfunction "XO_10") (pintype "output"))
      (node (ref "Y1") (pin "2") (pinfunction "2_2") (pintype "passive"))
    )
    (net (code "138") (name "Net-(U2-B1)") (class "Default")
      (node (ref "R18") (pin "2") (pinfunction "2_2") (pintype "passive"))
      (node (ref "U2") (pin "18") (pinfunction "B1_18") (pintype "passive"))
    )
    (net (code "139") (name "Net-(U2-B2)") (class "Default")
      (node (ref "R19") (pin "2") (pinfunction "2_2") (pintype "passive"))
      (node (ref "U2") (pin "17") (pinfunction "B2_17") (pintype "passive"))
    )
    (net (code "140") (name "Net-(U2-B3)") (class "Default")
      (node (ref "R20") (pin "2") (pinfunction "2_2") (pintype "passive"))
      (node (ref "U2") (pin "16") (pinfunction "B3_16") (pintype "passive"))
    )
    (net (code "141") (name "Net-(U2-B4)") (class "Default")
      (node (ref "R21") (pin "2") (pinfunction "2_2") (pintype "passive"))
      (node (ref "U2") (pin "15") (pinfunction "B4_15") (pintype "passive"))
    )
    (net (code "142") (name "Net-(U2-B5)") (class "Default")
      (node (ref "R22") (pin "2") (pinfunction "2_2") (pintype "passive"))
      (node (ref "U2") (pin "14") (pinfunction "B5_14") (pintype "passive"))
    )
    (net (code "143") (name "Net-(U2-B6)") (class "Default")
      (node (ref "R23") (pin "2") (pinfunction "2_2") (pintype "passive"))
      (node (ref "U2") (pin "13") (pinfunction "B6_13") (pintype "passive"))
    )
    (net (code "144") (name "Net-(U2-B7)") (class "Default")
      (node (ref "R24") (pin "2") (pinfunction "2_2") (pintype "passive"))
      (node (ref "U2") (pin "12") (pinfunction "B7_12") (pintype "passive"))
    )
    (net (code "145") (name "Net-(U2-B8)") (class "Default")
      (node (ref "R25") (pin "2") (pinfunction "2_2") (pintype "passive"))
      (node (ref "U2") (pin "11") (pinfunction "B8_11") (pintype "passive"))
    )
    (net (code "146") (name "Net-(U5-XTAL1)") (class "Default")
      (node (ref "C14") (pin "1") (pinfunction "1_1") (pintype "passive"))
      (node (ref "U5") (pin "19") (pinfunction "XTAL1_19") (pintype "passive"))
      (node (ref "Y2") (pin "2") (pinfunction "2_2") (pintype "passive"))
    )
    (net (code "147") (name "Net-(U5-XTAL2)") (class "Default")
      (node (ref "C15") (pin "1") (pinfunction "1_1") (pintype "passive"))
      (node (ref "U5") (pin "18") (pinfunction "XTAL2_18") (pintype "passive"))
      (node (ref "Y2") (pin "1") (pinfunction "1_1") (pintype "passive"))
    )
    (net (code "148") (name "Net-(U8-Vcc2)") (class "Default")
      (node (ref "C25") (pin "1") (pinfunction "1_1") (pintype "passive"))
      (node (ref "R6") (pin "1") (pinfunction "1_1") (pintype "passive"))
      (node (ref "U8") (pin "1") (pinfunction "Vcc2_1") (pintype "passive"))
    )
    (net (code "149") (name "Net-(U8-X1)") (class "Default")
      (node (ref "U8") (pin "2") (pinfunction "X1_2") (pintype "passive"))
      (node (ref "Y3") (pin "1") (pinfunction "1_1") (pintype "passive"))
    )
    (net (code "150") (name "Net-(U8-X2)") (class "Default")
      (node (ref "U8") (pin "3") (pinfunction "X2_3") (pintype "passive"))
      (node (ref "Y3") (pin "2") (pinfunction "2_2") (pintype "passive"))
    )
    (net (code "151") (name "Net-(U10-VDD)") (class "Default")
      (node (ref "C26") (pin "2") (pinfunction "2_2") (pintype "passive"))
      (node (ref "R69") (pin "1") (pinfunction "1_1") (pintype "passive"))
      (node (ref "U10") (pin "3") (pinfunction "VDD_3") (pintype "power_in"))
    )
    (net (code "152") (name "unconnected-(J10-Pad1)") (class "Default")
      (node (ref "J10") (pin "1") (pinfunction "1_1") (pintype "passive"))
    )
    (net (code "153") (name "unconnected-(J10-Pad4)") (class "Default")
      (node (ref "J10") (pin "4") (pinfunction "4_4") (pintype "passive"))
    )
    (net (code "154") (name "unconnected-(J17-Pad1)") (class "Default")
      (node (ref "J17") (pin "1") (pinfunction "1_1") (pintype "passive"))
    )
    (net (code "155") (name "unconnected-(LCD2-NC-Pad16)") (class "Default")
      (node (ref "LCD2") (pin "16") (pinfunction "NC_16") (pintype "power_in"))
    )
    (net (code "156") (name "unconnected-(LCD2-RST#-Pad17)") (class "Default")
      (node (ref "LCD2") (pin "17") (pinfunction "RST#_17") (pintype "power_in"))
    )
    (net (code "157") (name "unconnected-(LCD2-V0-Pad3)") (class "Default")
      (node (ref "LCD2") (pin "3") (pinfunction "V0_3") (pintype "power_in"))
    )
    (net (code "158") (name "unconnected-(LCD2-VOUT-Pad18)") (class "Default")
      (node (ref "LCD2") (pin "18") (pinfunction "VOUT_18") (pintype "power_in"))
    )
    (net (code "159") (name "unconnected-(U1-ACT#-Pad2)") (class "Default")
      (node (ref "U1") (pin "2") (pinfunction "ACT#_2") (pintype "output"))
    )
    (net (code "160") (name "unconnected-(U1-CKO-Pad1)") (class "Default")
      (node (ref "U1") (pin "1") (pinfunction "CKO_1") (pintype "output"))
    )
    (net (code "161") (name "unconnected-(U1-CTS#-Pad11)") (class "Default")
      (node (ref "U1") (pin "11") (pinfunction "CTS#_11") (pintype "input"))
    )
    (net (code "162") (name "unconnected-(U1-DCD#-Pad14)") (class "Default")
      (node (ref "U1") (pin "14") (pinfunction "DCD#_14") (pintype "input"))
    )
    (net (code "163") (name "unconnected-(U1-DSR#-Pad12)") (class "Default")
      (node (ref "U1") (pin "12") (pinfunction "DSR#_12") (pintype "input"))
    )
    (net (code "164") (name "unconnected-(U1-DTR#-Pad15)") (class "Default")
      (node (ref "U1") (pin "15") (pinfunction "DTR#_15") (pintype "output"))
    )
    (net (code "165") (name "unconnected-(U1-NC-Pad17)") (class "Default")
      (node (ref "U1") (pin "17") (pinfunction "NC_17") (pintype "passive"))
    )
    (net (code "166") (name "unconnected-(U1-NOS#-Pad20)") (class "Default")
      (node (ref "U1") (pin "20") (pinfunction "NOS#_20") (pintype "input"))
    )
    (net (code "167") (name "unconnected-(U1-R232-Pad18)") (class "Default")
      (node (ref "U1") (pin "18") (pinfunction "R232_18") (pintype "output"))
    )
    (net (code "168") (name "unconnected-(U1-RI#-Pad13)") (class "Default")
      (node (ref "U1") (pin "13") (pinfunction "RI#_13") (pintype "input"))
    )
    (net (code "169") (name "unconnected-(U1-RTS#-Pad16)") (class "Default")
      (node (ref "U1") (pin "16") (pinfunction "RTS#_16") (pintype "output"))
    )
    (net (code "170") (name "unconnected-(U3-~{Y7}-Pad7)") (class "Default")
      (node (ref "U3") (pin "7") (pinfunction "~{Y7}_7") (pintype "passive"))
    )
    (net (code "171") (name "unconnected-(U5-ALE-Pad30)") (class "Default")
      (node (ref "U5") (pin "30") (pinfunction "ALE_30") (pintype "passive"))
    )
    (net (code "172") (name "unconnected-(U5-~{PSEN}-Pad29)") (class "Default")
      (node (ref "U5") (pin "29") (pinfunction "~{PSEN}_29") (pintype "passive"))
    )
    (net (code "173") (name "unconnected-(U6-OSC-Pad11)") (class "Default")
      (node (ref "U6") (pin "11") (pinfunction "OSC_11") (pintype "passive"))
    )
  )
)
